# SmartToy_Main_Board_REV02_Schematic.net
KiCad netlist of a schematic drawn in Altium Designer
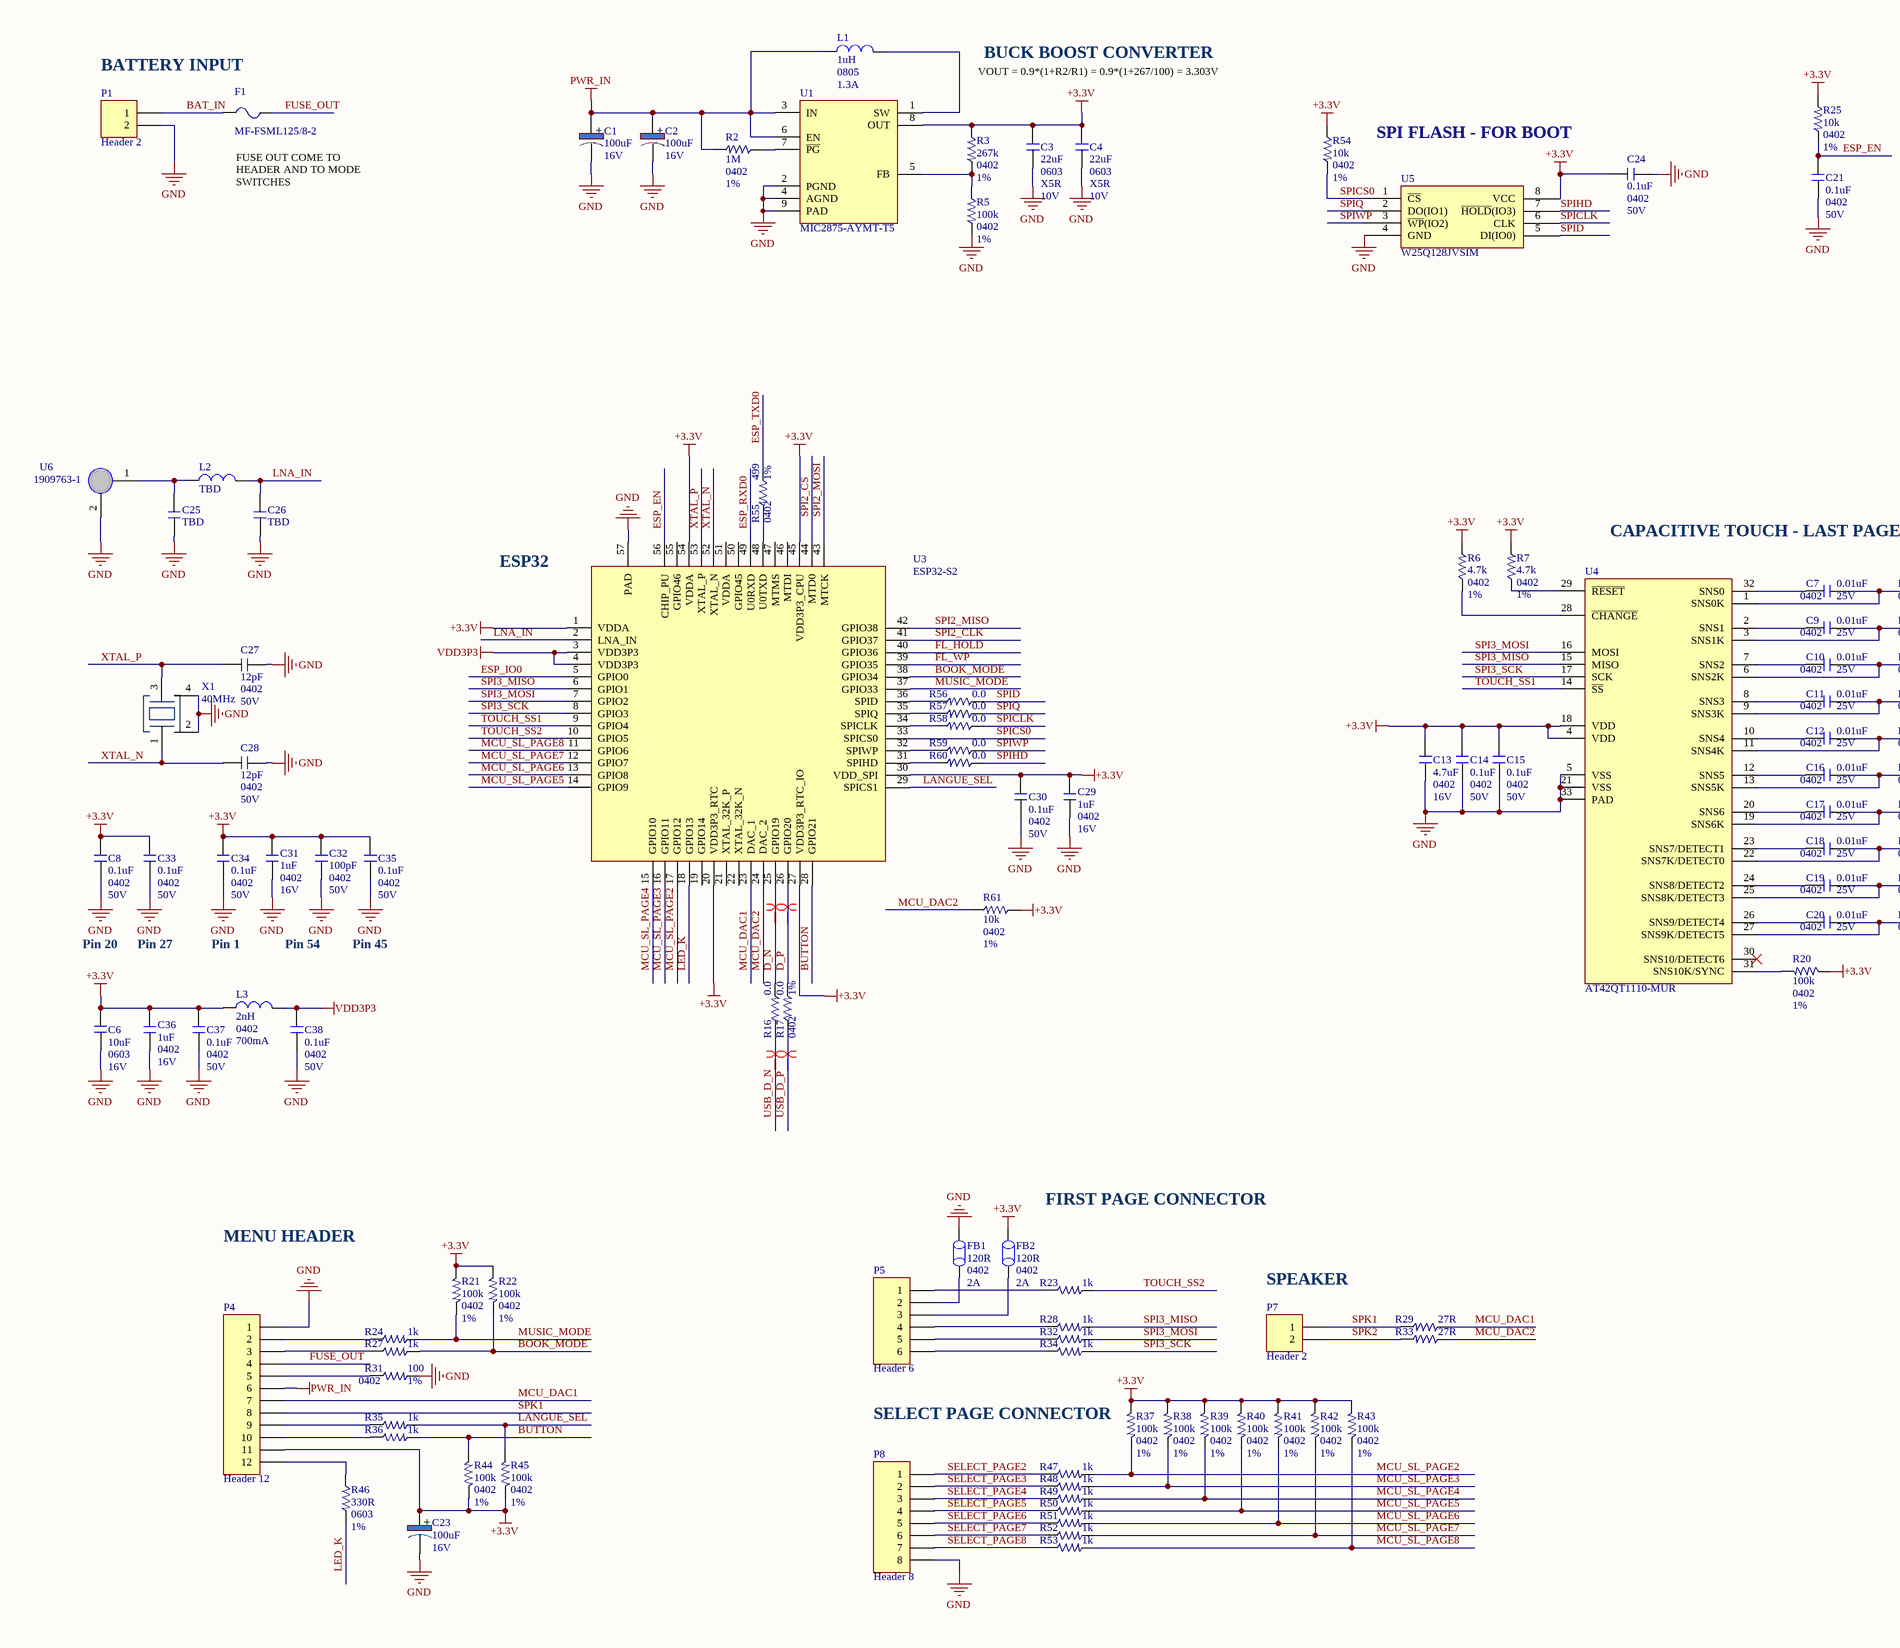
[diagram p0: SmartToy Main Board REV02 Schematic.SchDoc, left]
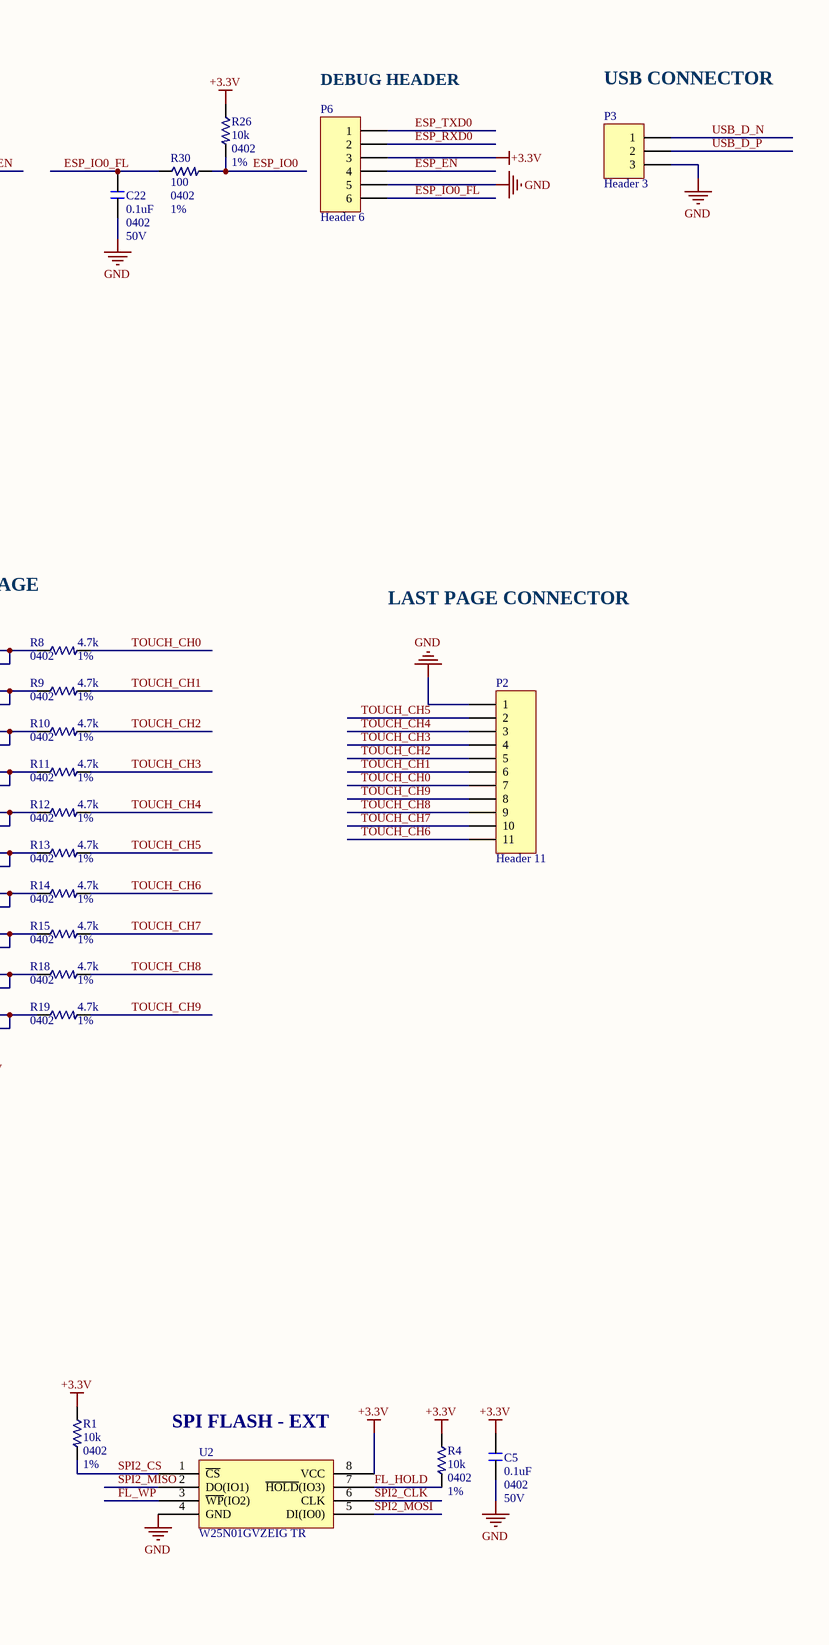
[diagram p1: SmartToy Main Board REV02 Schematic.SchDoc, right]

(export (version "E")
  (design (tool "Eeschema 10.0.6"))
  (components
    (comp (ref "C1")
      (value "100uF")
      (footprint "CP_6.3X12.5_P2.5MM")
      (description "CAP ALUM 100UF 20% 16V RADIAL")
      (fields
        (field (name "TOLERANCE") "20%")
        (field (name "VOLTAGE RATING") "16V")
        (field (name "VOLTAGE") "16V")
      )
      (libsource (lib "CommonLib") (part "CAP_PL"))
    )
    (comp (ref "C2")
      (value "100uF")
      (footprint "CP_6.3X12.5_P2.5MM")
      (description "CAP ALUM 100UF 20% 16V RADIAL")
      (fields
        (field (name "TOLERANCE") "20%")
        (field (name "VOLTAGE RATING") "16V")
        (field (name "VOLTAGE") "16V")
      )
      (libsource (lib "CommonLib") (part "CAP_PL"))
    )
    (comp (ref "C3")
      (value "22uF")
      (footprint "C0603M")
      (description "CAP CER 22UF 10V X5R 0603")
      (fields
        (field (name "MANUFACTURER") "Samsung")
        (field (name "MANUFACTURER PART NUMBER") "CL10A226MP8NUNE")
        (field (name "CASE CODE (IMPERIAL)") "0603")
        (field (name "DIELECTRIC") "X5R")
        (field (name "VOLTAGE RATING") "10V")
      )
      (libsource (lib "CommonLib") (part "CAP_CER"))
    )
    (comp (ref "C4")
      (value "22uF")
      (footprint "C0603M")
      (description "CAP CER 22UF 10V X5R 0603")
      (fields
        (field (name "MANUFACTURER") "Samsung")
        (field (name "MANUFACTURER PART NUMBER") "CL10A226MP8NUNE")
        (field (name "CASE CODE (IMPERIAL)") "0603")
        (field (name "DIELECTRIC") "X5R")
        (field (name "VOLTAGE RATING") "10V")
      )
      (libsource (lib "CommonLib") (part "CAP_CER"))
    )
    (comp (ref "C5")
      (value "0.1uF")
      (footprint "C0402M")
      (description "CAP CER 0.1UF 50V X7R 0402")
      (fields
        (field (name "MANUFACTURER") "Murata")
        (field (name "MANUFACTURER PART NUMBER") "GRM155R71H104KE14D")
        (field (name "CASE CODE (IMPERIAL)") "0402")
        (field (name "VOLTAGE") "50V")
      )
      (libsource (lib "CommonLib") (part "CAP_CER"))
    )
    (comp (ref "C6")
      (value "10uF")
      (footprint "C0603M")
      (description "CAP CER 10UF 16V X5R 0603")
      (fields
        (field (name "MANUFACTURER") "Taiyo Yuden")
        (field (name "MANUFACTURER PART NUMBER") "EMK107BBJ106MA-T")
        (field (name "CASE/PACKAGE") "0603")
        (field (name "VOLTAGE RATING (DC)") "16V")
      )
      (libsource (lib "CommonLib") (part "CAP_CER"))
    )
    (comp (ref "C7")
      (value "0.01uF")
      (footprint "C0402M")
      (description "CAP CER 10000PF 25V X7R 0402")
      (fields
        (field (name "MANUFACTURER") "Samsung")
        (field (name "MANUFACTURER PART NUMBER") "CL05B103KA5NNNC")
        (field (name "CASE/PACKAGE") "0402")
        (field (name "VOLTAGE RATING") "25V")
      )
      (libsource (lib "CommonLib") (part "CAP_CER"))
    )
    (comp (ref "C8")
      (value "0.1uF")
      (footprint "C0402M")
      (description "CAP CER 0.1UF 50V X7R 0402")
      (fields
        (field (name "MANUFACTURER") "Murata")
        (field (name "MANUFACTURER PART NUMBER") "GRM155R71H104KE14D")
        (field (name "CASE CODE (IMPERIAL)") "0402")
        (field (name "VOLTAGE") "50V")
      )
      (libsource (lib "CommonLib") (part "CAP_CER"))
    )
    (comp (ref "C9")
      (value "0.01uF")
      (footprint "C0402M")
      (description "CAP CER 10000PF 25V X7R 0402")
      (fields
        (field (name "MANUFACTURER") "Samsung")
        (field (name "MANUFACTURER PART NUMBER") "CL05B103KA5NNNC")
        (field (name "CASE/PACKAGE") "0402")
        (field (name "VOLTAGE RATING") "25V")
      )
      (libsource (lib "CommonLib") (part "CAP_CER"))
    )
    (comp (ref "C10")
      (value "0.01uF")
      (footprint "C0402M")
      (description "CAP CER 10000PF 25V X7R 0402")
      (fields
        (field (name "MANUFACTURER") "Samsung")
        (field (name "MANUFACTURER PART NUMBER") "CL05B103KA5NNNC")
        (field (name "CASE/PACKAGE") "0402")
        (field (name "VOLTAGE RATING") "25V")
      )
      (libsource (lib "CommonLib") (part "CAP_CER"))
    )
    (comp (ref "C11")
      (value "0.01uF")
      (footprint "C0402M")
      (description "CAP CER 10000PF 25V X7R 0402")
      (fields
        (field (name "MANUFACTURER") "Samsung")
        (field (name "MANUFACTURER PART NUMBER") "CL05B103KA5NNNC")
        (field (name "CASE/PACKAGE") "0402")
        (field (name "VOLTAGE RATING") "25V")
      )
      (libsource (lib "CommonLib") (part "CAP_CER"))
    )
    (comp (ref "C12")
      (value "0.01uF")
      (footprint "C0402M")
      (description "CAP CER 10000PF 25V X7R 0402")
      (fields
        (field (name "MANUFACTURER") "Samsung")
        (field (name "MANUFACTURER PART NUMBER") "CL05B103KA5NNNC")
        (field (name "CASE/PACKAGE") "0402")
        (field (name "VOLTAGE RATING") "25V")
      )
      (libsource (lib "CommonLib") (part "CAP_CER"))
    )
    (comp (ref "C13")
      (value "4.7uF")
      (footprint "C0402M")
      (description "CAP CER 4.7UF 16V X5R 0402")
      (fields
        (field (name "MANUFACTURER") "Samsung")
        (field (name "MANUFACTURER PART NUMBER") "CL05A475MO5NUNC")
        (field (name "CASE/PACKAGE") "0402")
        (field (name "VOLTAGE RATING") "16V")
      )
      (libsource (lib "CommonLib") (part "CAP_CER"))
    )
    (comp (ref "C14")
      (value "0.1uF")
      (footprint "C0402M")
      (description "CAP CER 0.1UF 50V X7R 0402")
      (fields
        (field (name "MANUFACTURER") "Murata")
        (field (name "MANUFACTURER PART NUMBER") "GRM155R71H104KE14D")
        (field (name "CASE/PACKAGE") "0402")
        (field (name "VOLTAGE") "50V")
      )
      (libsource (lib "CommonLib") (part "CAP_CER"))
    )
    (comp (ref "C15")
      (value "0.1uF")
      (footprint "C0402M")
      (description "CAP CER 0.1UF 50V X7R 0402")
      (fields
        (field (name "MANUFACTURER") "Murata")
        (field (name "MANUFACTURER PART NUMBER") "GRM155R71H104KE14D")
        (field (name "CASE/PACKAGE") "0402")
        (field (name "VOLTAGE") "50V")
      )
      (libsource (lib "CommonLib") (part "CAP_CER"))
    )
    (comp (ref "C16")
      (value "0.01uF")
      (footprint "C0402M")
      (description "CAP CER 10000PF 25V X7R 0402")
      (fields
        (field (name "MANUFACTURER") "Samsung")
        (field (name "MANUFACTURER PART NUMBER") "CL05B103KA5NNNC")
        (field (name "CASE/PACKAGE") "0402")
        (field (name "VOLTAGE RATING") "25V")
      )
      (libsource (lib "CommonLib") (part "CAP_CER"))
    )
    (comp (ref "C17")
      (value "0.01uF")
      (footprint "C0402M")
      (description "CAP CER 10000PF 25V X7R 0402")
      (fields
        (field (name "MANUFACTURER") "Samsung")
        (field (name "MANUFACTURER PART NUMBER") "CL05B103KA5NNNC")
        (field (name "CASE/PACKAGE") "0402")
        (field (name "VOLTAGE RATING") "25V")
      )
      (libsource (lib "CommonLib") (part "CAP_CER"))
    )
    (comp (ref "C18")
      (value "0.01uF")
      (footprint "C0402M")
      (description "CAP CER 10000PF 25V X7R 0402")
      (fields
        (field (name "MANUFACTURER") "Samsung")
        (field (name "MANUFACTURER PART NUMBER") "CL05B103KA5NNNC")
        (field (name "CASE/PACKAGE") "0402")
        (field (name "VOLTAGE RATING") "25V")
      )
      (libsource (lib "CommonLib") (part "CAP_CER"))
    )
    (comp (ref "C19")
      (value "0.01uF")
      (footprint "C0402M")
      (description "CAP CER 10000PF 25V X7R 0402")
      (fields
        (field (name "MANUFACTURER") "Samsung")
        (field (name "MANUFACTURER PART NUMBER") "CL05B103KA5NNNC")
        (field (name "CASE/PACKAGE") "0402")
        (field (name "VOLTAGE RATING") "25V")
      )
      (libsource (lib "CommonLib") (part "CAP_CER"))
    )
    (comp (ref "C20")
      (value "0.01uF")
      (footprint "C0402M")
      (description "CAP CER 10000PF 25V X7R 0402")
      (fields
        (field (name "MANUFACTURER") "Samsung")
        (field (name "MANUFACTURER PART NUMBER") "CL05B103KA5NNNC")
        (field (name "CASE/PACKAGE") "0402")
        (field (name "VOLTAGE RATING") "25V")
      )
      (libsource (lib "CommonLib") (part "CAP_CER"))
    )
    (comp (ref "C21")
      (value "0.1uF")
      (footprint "C0402M")
      (description "CAP CER 0.1UF 50V X7R 0402")
      (fields
        (field (name "MANUFACTURER") "Murata")
        (field (name "MANUFACTURER PART NUMBER") "GRM155R71H104KE14D")
        (field (name "CASE CODE (IMPERIAL)") "0402")
        (field (name "VOLTAGE") "50V")
      )
      (libsource (lib "CommonLib") (part "CAP_CER"))
    )
    (comp (ref "C22")
      (value "0.1uF")
      (footprint "C0402M")
      (description "CAP CER 0.1UF 50V X7R 0402")
      (fields
        (field (name "MANUFACTURER") "Murata")
        (field (name "MANUFACTURER PART NUMBER") "GRM155R71H104KE14D")
        (field (name "CASE CODE (IMPERIAL)") "0402")
        (field (name "VOLTAGE") "50V")
      )
      (libsource (lib "CommonLib") (part "CAP_CER"))
    )
    (comp (ref "C23")
      (value "100uF")
      (footprint "CP_6.3X12.5_P2.5MM")
      (description "CAP ALUM 100UF 20% 16V RADIAL")
      (fields
        (field (name "TOLERANCE") "20%")
        (field (name "VOLTAGE RATING") "16V")
        (field (name "VOLTAGE") "16V")
      )
      (libsource (lib "CommonLib") (part "CAP_PL"))
    )
    (comp (ref "C24")
      (value "0.1uF")
      (footprint "C0402M")
      (description "CAP CER 0.1UF 50V X7R 0402")
      (fields
        (field (name "MANUFACTURER") "Murata")
        (field (name "MANUFACTURER PART NUMBER") "GRM155R71H104KE14D")
        (field (name "CASE CODE (IMPERIAL)") "0402")
        (field (name "VOLTAGE") "50V")
      )
      (libsource (lib "CommonLib") (part "CAP_CER"))
    )
    (comp (ref "C25")
      (value "TBD")
      (footprint "C0402M")
      (description "CERAMIC CAPACITOR")
      (libsource (lib "") (part "CAP_CER_1"))
    )
    (comp (ref "C26")
      (value "TBD")
      (footprint "C0402M")
      (description "CERAMIC CAPACITOR")
      (libsource (lib "") (part "CAP_CER_1"))
    )
    (comp (ref "C27")
      (value "12pF")
      (footprint "C0402M")
      (description "CAP CER 12PF 50V C0G/NP0 0402")
      (fields
        (field (name "MANUFACTURER") "Murata")
        (field (name "MANUFACTURER PART NUMBER") "GRM1555C1H120JA01J")
        (field (name "CASE/PACKAGE") "0402")
        (field (name "VOLTAGE RATING") "50V")
      )
      (libsource (lib "CommonLib") (part "CAP_CER"))
    )
    (comp (ref "C28")
      (value "12pF")
      (footprint "C0402M")
      (description "CAP CER 12PF 50V C0G/NP0 0402")
      (fields
        (field (name "MANUFACTURER") "Murata")
        (field (name "MANUFACTURER PART NUMBER") "GRM1555C1H120JA01J")
        (field (name "CASE/PACKAGE") "0402")
        (field (name "VOLTAGE RATING") "50V")
      )
      (libsource (lib "CommonLib") (part "CAP_CER"))
    )
    (comp (ref "C29")
      (value "1uF")
      (footprint "C0402M")
      (description "CAP CER 1UF 16V X5R 0402")
      (fields
        (field (name "CASE/PACKAGE") "0402")
        (field (name "VOLTAGE RATING") "16V")
        (field (name "TOLERANCE") "20%")
      )
      (libsource (lib "") (part "CAP_CER_1"))
    )
    (comp (ref "C30")
      (value "0.1uF")
      (footprint "C0402M")
      (description "CAP CER 0.1UF 50V X7R 0402")
      (fields
        (field (name "MANUFACTURER") "Murata")
        (field (name "MANUFACTURER PART NUMBER") "GRM155R71H104KE14D")
        (field (name "CASE CODE (IMPERIAL)") "0402")
        (field (name "VOLTAGE") "50V")
      )
      (libsource (lib "CommonLib") (part "CAP_CER"))
    )
    (comp (ref "C31")
      (value "1uF")
      (footprint "C0402M")
      (description "CAP CER 1UF 16V X5R 0402")
      (fields
        (field (name "CASE/PACKAGE") "0402")
        (field (name "VOLTAGE RATING") "16V")
        (field (name "TOLERANCE") "20%")
      )
      (libsource (lib "") (part "CAP_CER_1"))
    )
    (comp (ref "C32")
      (value "100pF")
      (footprint "C0402M")
      (description "CAP CER 100PF 50V X7R 0402")
      (fields
        (field (name "CASE/PACKAGE") "0402")
        (field (name "TOLERANCE") "10%")
        (field (name "VOLTAGE RATING (DC)") "50V")
        (field (name "VOLTAGE") "50V")
      )
      (libsource (lib "") (part "CAP_CER_1"))
    )
    (comp (ref "C33")
      (value "0.1uF")
      (footprint "C0402M")
      (description "CAP CER 0.1UF 50V X7R 0402")
      (fields
        (field (name "MANUFACTURER") "Murata")
        (field (name "MANUFACTURER PART NUMBER") "GRM155R71H104KE14D")
        (field (name "CASE CODE (IMPERIAL)") "0402")
        (field (name "VOLTAGE") "50V")
      )
      (libsource (lib "CommonLib") (part "CAP_CER"))
    )
    (comp (ref "C34")
      (value "0.1uF")
      (footprint "C0402M")
      (description "CAP CER 0.1UF 50V X7R 0402")
      (fields
        (field (name "MANUFACTURER") "Murata")
        (field (name "MANUFACTURER PART NUMBER") "GRM155R71H104KE14D")
        (field (name "CASE CODE (IMPERIAL)") "0402")
        (field (name "VOLTAGE") "50V")
      )
      (libsource (lib "CommonLib") (part "CAP_CER"))
    )
    (comp (ref "C35")
      (value "0.1uF")
      (footprint "C0402M")
      (description "CAP CER 0.1UF 50V X7R 0402")
      (fields
        (field (name "MANUFACTURER") "Murata")
        (field (name "MANUFACTURER PART NUMBER") "GRM155R71H104KE14D")
        (field (name "CASE CODE (IMPERIAL)") "0402")
        (field (name "VOLTAGE") "50V")
      )
      (libsource (lib "CommonLib") (part "CAP_CER"))
    )
    (comp (ref "C36")
      (value "1uF")
      (footprint "C0402M")
      (description "CAP CER 1UF 16V X5R 0402")
      (fields
        (field (name "CASE/PACKAGE") "0402")
        (field (name "VOLTAGE RATING") "16V")
        (field (name "TOLERANCE") "20%")
      )
      (libsource (lib "") (part "CAP_CER_1"))
    )
    (comp (ref "C37")
      (value "0.1uF")
      (footprint "C0402M")
      (description "CAP CER 0.1UF 50V X7R 0402")
      (fields
        (field (name "MANUFACTURER") "Murata")
        (field (name "MANUFACTURER PART NUMBER") "GRM155R71H104KE14D")
        (field (name "CASE CODE (IMPERIAL)") "0402")
        (field (name "VOLTAGE") "50V")
      )
      (libsource (lib "CommonLib") (part "CAP_CER"))
    )
    (comp (ref "C38")
      (value "0.1uF")
      (footprint "C0402M")
      (description "CAP CER 0.1UF 50V X7R 0402")
      (fields
        (field (name "MANUFACTURER") "Murata")
        (field (name "MANUFACTURER PART NUMBER") "GRM155R71H104KE14D")
        (field (name "CASE CODE (IMPERIAL)") "0402")
        (field (name "VOLTAGE") "50V")
      )
      (libsource (lib "CommonLib") (part "CAP_CER"))
    )
    (comp (ref "F1")
      (value "MF-FSML125/8-2")
      (footprint "R0603M")
      (description "PTC RESET FUSE 8V 1.25A 0603")
      (libsource (lib "CommonLib") (part "FUSE"))
    )
    (comp (ref "FB1")
      (value "120R")
      (footprint "R0402M")
      (description "FERRITE BEAD 120 OHM 0402 1LN")
      (fields
        (field (name "MANUFACTURER") "Murata")
        (field (name "MANUFACTURER PART NUMBER") "BLM15PX121SN1D")
        (field (name "CASE/PACKAGE") "0402")
        (field (name "CURRENT RATING") "2A")
      )
      (libsource (lib "CommonLib") (part "FB"))
    )
    (comp (ref "FB2")
      (value "120R")
      (footprint "R0402M")
      (description "FERRITE BEAD 120 OHM 0402 1LN")
      (fields
        (field (name "MANUFACTURER") "Murata")
        (field (name "MANUFACTURER PART NUMBER") "BLM15PX121SN1D")
        (field (name "CASE/PACKAGE") "0402")
        (field (name "CURRENT RATING") "2A")
      )
      (libsource (lib "CommonLib") (part "FB"))
    )
    (comp (ref "L1")
      (value "1uH")
      (footprint "IND_0805")
      (description "FIXED IND 1UH 1.3A 82.5 MOHM SMD")
      (fields
        (field (name "CASE CODE (IMPERIAL)") "0805")
        (field (name "TOLERANCE") "30%")
        (field (name "CURRENT RATING") "1.3A")
      )
      (libsource (lib "CommonLib") (part "IND_SMD"))
    )
    (comp (ref "L2")
      (value "TBD")
      (footprint "IND_0402")
      (description "INDUCTOR SMD")
      (libsource (lib "CommonLib") (part "IND_SMD"))
    )
    (comp (ref "L3")
      (value "2nH")
      (footprint "IND_0402")
      (description "FIXED IND 2NH 700MA 120 MOHM SMD")
      (fields (field (name "CASE CODE (IMPERIAL)") "0402") (field (name "CURRENT RATING") "700mA"))
      (libsource (lib "CommonLib") (part "IND_SMD"))
    )
    (comp (ref "P1")
      (value "Header 2")
      (footprint "HDR1X2")
      (description "Header, 2-Pin")
      (fields (field (name "PUBLISHER") "Altium Limited"))
      (libsource (lib "Miscellaneous Connectors") (part "Header 2"))
    )
    (comp (ref "P2")
      (value "Header 11")
      (footprint "TOUCH_CONTACT_MAINBOARD")
      (description "Header, 11-Pin")
      (fields (field (name "PUBLISHER") "Altium Limited"))
      (libsource (lib "Miscellaneous Connectors") (part "Header 11"))
    )
    (comp (ref "P3")
      (value "Header 3")
      (footprint "HDR1X3")
      (description "Header, 3-Pin")
      (fields (field (name "PUBLISHER") "Altium Limited"))
      (libsource (lib "Miscellaneous Connectors") (part "Header 3"))
    )
    (comp (ref "P4")
      (value "Header 12")
      (footprint "HDR1X12")
      (description "Header, 12-Pin")
      (fields (field (name "PUBLISHER") "Altium Limited"))
      (libsource (lib "Miscellaneous Connectors") (part "Header 12"))
    )
    (comp (ref "P5")
      (value "Header 6")
      (footprint "HDR1X6")
      (description "Header, 6-Pin")
      (fields (field (name "PUBLISHER") "Altium Limited"))
      (libsource (lib "Miscellaneous Connectors") (part "Header 6"))
    )
    (comp (ref "P6")
      (value "Header 6")
      (footprint "HDR1X6")
      (description "Header, 6-Pin")
      (fields (field (name "PUBLISHER") "Altium Limited"))
      (libsource (lib "Miscellaneous Connectors") (part "Header 6"))
    )
    (comp (ref "P7")
      (value "Header 2")
      (footprint "HDR1X2")
      (description "Header, 2-Pin")
      (fields (field (name "PUBLISHER") "Altium Limited"))
      (libsource (lib "Miscellaneous Connectors") (part "Header 2"))
    )
    (comp (ref "P8")
      (value "Header 8")
      (footprint "HDR1X8")
      (description "Header, 8-Pin")
      (fields (field (name "PUBLISHER") "Altium Limited"))
      (libsource (lib "Miscellaneous Connectors") (part "Header 8"))
    )
    (comp (ref "R1")
      (value "10k")
      (footprint "R0402M")
      (description "RES SMD 10K OHM 1% 1/16W 0402")
      (fields
        (field (name "MANUFACTURER") "Yageo")
        (field (name "MANUFACTURER PART NUMBER") "RC0402FR-0710KL")
        (field (name "CASE CODE (IMPERIAL)") "0402")
        (field (name "TOLERANCE") "1%")
      )
      (libsource (lib "CommonLib") (part "RES_SMD"))
    )
    (comp (ref "R2")
      (value "1M")
      (footprint "R0402M")
      (description "RES SMD 1M OHM 1% 1/16W 0402")
      (fields (field (name "SIZE CODE") "0402") (field (name "TOLERANCE") "1%"))
      (libsource (lib "CommonLib") (part "RES_SMD"))
    )
    (comp (ref "R3")
      (value "267k")
      (footprint "R0402M")
      (description "RES SMD 267k OHM 1% 1/16W 0402")
      (fields (field (name "CASE/PACKAGE") "0402") (field (name "TOLERANCE") "1%"))
      (libsource (lib "CommonLib") (part "RES_SMD"))
    )
    (comp (ref "R4")
      (value "10k")
      (footprint "R0402M")
      (description "RES SMD 10K OHM 1% 1/16W 0402")
      (fields
        (field (name "MANUFACTURER") "Yageo")
        (field (name "MANUFACTURER PART NUMBER") "RC0402FR-0710KL")
        (field (name "CASE CODE (IMPERIAL)") "0402")
        (field (name "TOLERANCE") "1%")
      )
      (libsource (lib "CommonLib") (part "RES_SMD"))
    )
    (comp (ref "R5")
      (value "100k")
      (footprint "R0402M")
      (description "RES SMD 100K OHM 1% 1/16W 0402")
      (fields
        (field (name "CASE/PACKAGE") "0402")
        (field (name "TOLERANCE") "1%")
        (field (name "RESISTANCE TOLERANCE") "1%")
      )
      (libsource (lib "CommonLib") (part "RES_SMD"))
    )
    (comp (ref "R6")
      (value "4.7k")
      (footprint "R0402M")
      (description "RES SMD 4.7K OHM 1% 1/16W 0402")
      (fields
        (field (name "MANUFACTURER") "Yageo")
        (field (name "MANUFACTURER PART NUMBER") "RC0402FR-074K7L")
        (field (name "CASE CODE (IMPERIAL)") "0402")
        (field (name "TOLERANCE") "1%")
      )
      (libsource (lib "CommonLib") (part "RES_SMD"))
    )
    (comp (ref "R7")
      (value "4.7k")
      (footprint "R0402M")
      (description "RES SMD 4.7K OHM 1% 1/16W 0402")
      (fields
        (field (name "MANUFACTURER") "Yageo")
        (field (name "MANUFACTURER PART NUMBER") "RC0402FR-074K7L")
        (field (name "CASE CODE (IMPERIAL)") "0402")
        (field (name "TOLERANCE") "1%")
      )
      (libsource (lib "CommonLib") (part "RES_SMD"))
    )
    (comp (ref "R8")
      (value "4.7k")
      (footprint "R0402M")
      (description "RES SMD 4.7K OHM 1% 1/16W 0402")
      (fields
        (field (name "MANUFACTURER") "Yageo")
        (field (name "MANUFACTURER PART NUMBER") "RC0402FR-074K7L")
        (field (name "CASE CODE (IMPERIAL)") "0402")
        (field (name "TOLERANCE") "1%")
      )
      (libsource (lib "CommonLib") (part "RES_SMD"))
    )
    (comp (ref "R9")
      (value "4.7k")
      (footprint "R0402M")
      (description "RES SMD 4.7K OHM 1% 1/16W 0402")
      (fields
        (field (name "MANUFACTURER") "Yageo")
        (field (name "MANUFACTURER PART NUMBER") "RC0402FR-074K7L")
        (field (name "CASE CODE (IMPERIAL)") "0402")
        (field (name "TOLERANCE") "1%")
      )
      (libsource (lib "CommonLib") (part "RES_SMD"))
    )
    (comp (ref "R10")
      (value "4.7k")
      (footprint "R0402M")
      (description "RES SMD 4.7K OHM 1% 1/16W 0402")
      (fields
        (field (name "MANUFACTURER") "Yageo")
        (field (name "MANUFACTURER PART NUMBER") "RC0402FR-074K7L")
        (field (name "CASE CODE (IMPERIAL)") "0402")
        (field (name "TOLERANCE") "1%")
      )
      (libsource (lib "CommonLib") (part "RES_SMD"))
    )
    (comp (ref "R11")
      (value "4.7k")
      (footprint "R0402M")
      (description "RES SMD 4.7K OHM 1% 1/16W 0402")
      (fields
        (field (name "MANUFACTURER") "Yageo")
        (field (name "MANUFACTURER PART NUMBER") "RC0402FR-074K7L")
        (field (name "CASE CODE (IMPERIAL)") "0402")
        (field (name "TOLERANCE") "1%")
      )
      (libsource (lib "CommonLib") (part "RES_SMD"))
    )
    (comp (ref "R12")
      (value "4.7k")
      (footprint "R0402M")
      (description "RES SMD 4.7K OHM 1% 1/16W 0402")
      (fields
        (field (name "MANUFACTURER") "Yageo")
        (field (name "MANUFACTURER PART NUMBER") "RC0402FR-074K7L")
        (field (name "CASE CODE (IMPERIAL)") "0402")
        (field (name "TOLERANCE") "1%")
      )
      (libsource (lib "CommonLib") (part "RES_SMD"))
    )
    (comp (ref "R13")
      (value "4.7k")
      (footprint "R0402M")
      (description "RES SMD 4.7K OHM 1% 1/16W 0402")
      (fields
        (field (name "MANUFACTURER") "Yageo")
        (field (name "MANUFACTURER PART NUMBER") "RC0402FR-074K7L")
        (field (name "CASE CODE (IMPERIAL)") "0402")
        (field (name "TOLERANCE") "1%")
      )
      (libsource (lib "CommonLib") (part "RES_SMD"))
    )
    (comp (ref "R14")
      (value "4.7k")
      (footprint "R0402M")
      (description "RES SMD 4.7K OHM 1% 1/16W 0402")
      (fields
        (field (name "MANUFACTURER") "Yageo")
        (field (name "MANUFACTURER PART NUMBER") "RC0402FR-074K7L")
        (field (name "CASE CODE (IMPERIAL)") "0402")
        (field (name "TOLERANCE") "1%")
      )
      (libsource (lib "CommonLib") (part "RES_SMD"))
    )
    (comp (ref "R15")
      (value "4.7k")
      (footprint "R0402M")
      (description "RES SMD 4.7K OHM 1% 1/16W 0402")
      (fields
        (field (name "MANUFACTURER") "Yageo")
        (field (name "MANUFACTURER PART NUMBER") "RC0402FR-074K7L")
        (field (name "CASE CODE (IMPERIAL)") "0402")
        (field (name "TOLERANCE") "1%")
      )
      (libsource (lib "CommonLib") (part "RES_SMD"))
    )
    (comp (ref "R16")
      (value "0.0")
      (footprint "R0402M")
      (description "RES SMD 0 OHM JUMPER 1/16W 0402")
      (fields
        (field (name "MANUFACTURER") "Yageo")
        (field (name "MANUFACTURER PART NUMBER") "RC0402FR-070RL")
      )
      (libsource (lib "CommonLib") (part "RES_SMD"))
    )
    (comp (ref "R17")
      (value "0.0")
      (footprint "R0402M")
      (description "RES SMD 0 OHM JUMPER 1/16W 0402")
      (fields
        (field (name "MANUFACTURER") "Yageo")
        (field (name "MANUFACTURER PART NUMBER") "RC0402FR-070RL")
        (field (name "CASE CODE (IMPERIAL)") "0402")
        (field (name "TOLERANCE") "1%")
      )
      (libsource (lib "CommonLib") (part "RES_SMD"))
    )
    (comp (ref "R18")
      (value "4.7k")
      (footprint "R0402M")
      (description "RES SMD 4.7K OHM 1% 1/16W 0402")
      (fields
        (field (name "MANUFACTURER") "Yageo")
        (field (name "MANUFACTURER PART NUMBER") "RC0402FR-074K7L")
        (field (name "CASE CODE (IMPERIAL)") "0402")
        (field (name "TOLERANCE") "1%")
      )
      (libsource (lib "CommonLib") (part "RES_SMD"))
    )
    (comp (ref "R19")
      (value "4.7k")
      (footprint "R0402M")
      (description "RES SMD 4.7K OHM 1% 1/16W 0402")
      (fields
        (field (name "MANUFACTURER") "Yageo")
        (field (name "MANUFACTURER PART NUMBER") "RC0402FR-074K7L")
        (field (name "CASE CODE (IMPERIAL)") "0402")
        (field (name "TOLERANCE") "1%")
      )
      (libsource (lib "CommonLib") (part "RES_SMD"))
    )
    (comp (ref "R20")
      (value "100k")
      (footprint "R0402M")
      (description "RES SMD 100K OHM 1% 1/16W 0402")
      (fields
        (field (name "MANUFACTURER") "Yageo")
        (field (name "MANUFACTURER PART NUMBER") "RC0402FR-07100KL")
        (field (name "CASE CODE (IMPERIAL)") "0402")
        (field (name "TOLERANCE") "1%")
      )
      (libsource (lib "BLE1") (part "RES_SMD"))
    )
    (comp (ref "R21")
      (value "100k")
      (footprint "R0402M")
      (description "RES SMD 100K OHM 1% 1/16W 0402")
      (fields
        (field (name "MANUFACTURER") "Yageo")
        (field (name "MANUFACTURER PART NUMBER") "RC0402FR-07100KL")
        (field (name "CASE CODE (IMPERIAL)") "0402")
        (field (name "TOLERANCE") "1%")
      )
      (libsource (lib "BLE1") (part "RES_SMD"))
    )
    (comp (ref "R22")
      (value "100k")
      (footprint "R0402M")
      (description "RES SMD 100K OHM 1% 1/16W 0402")
      (fields
        (field (name "MANUFACTURER") "Yageo")
        (field (name "MANUFACTURER PART NUMBER") "RC0402FR-07100KL")
        (field (name "CASE CODE (IMPERIAL)") "0402")
        (field (name "TOLERANCE") "1%")
      )
      (libsource (lib "BLE1") (part "RES_SMD"))
    )
    (comp (ref "R23")
      (value "1k")
      (footprint "R0402M")
      (description "Surface Mount Chip Resistor, Thick Film, RC Series, 1 kohm, 62.5 mW, 1%, 50 V, 0402 [1005 Metric]")
      (fields (field (name "TOLERANCE") "1%"))
      (libsource (lib "CommonLib") (part "RES_SMD"))
    )
    (comp (ref "R24")
      (value "1k")
      (footprint "R0402M")
      (description "Surface Mount Chip Resistor, Thick Film, RC Series, 1 kohm, 62.5 mW, 1%, 50 V, 0402 [1005 Metric]")
      (fields (field (name "TOLERANCE") "1%"))
      (libsource (lib "CommonLib") (part "RES_SMD"))
    )
    (comp (ref "R25")
      (value "10k")
      (footprint "R0402M")
      (description "RES SMD 10K OHM 1% 1/16W 0402")
      (fields
        (field (name "MANUFACTURER") "Yageo")
        (field (name "MANUFACTURER PART NUMBER") "RC0402FR-0710KL")
        (field (name "CASE CODE (IMPERIAL)") "0402")
        (field (name "TOLERANCE") "1%")
      )
      (libsource (lib "CommonLib") (part "RES_SMD"))
    )
    (comp (ref "R26")
      (value "10k")
      (footprint "R0402M")
      (description "RES SMD 10K OHM 1% 1/16W 0402")
      (fields
        (field (name "MANUFACTURER") "Yageo")
        (field (name "MANUFACTURER PART NUMBER") "RC0402FR-0710KL")
        (field (name "CASE CODE (IMPERIAL)") "0402")
        (field (name "TOLERANCE") "1%")
      )
      (libsource (lib "CommonLib") (part "RES_SMD"))
    )
    (comp (ref "R27")
      (value "1k")
      (footprint "R0402M")
      (description "Surface Mount Chip Resistor, Thick Film, RC Series, 1 kohm, 62.5 mW, 1%, 50 V, 0402 [1005 Metric]")
      (fields (field (name "TOLERANCE") "1%"))
      (libsource (lib "CommonLib") (part "RES_SMD"))
    )
    (comp (ref "R28")
      (value "1k")
      (footprint "R0402M")
      (description "Surface Mount Chip Resistor, Thick Film, RC Series, 1 kohm, 62.5 mW, 1%, 50 V, 0402 [1005 Metric]")
      (fields (field (name "TOLERANCE") "1%"))
      (libsource (lib "CommonLib") (part "RES_SMD"))
    )
    (comp (ref "R29")
      (value "27R")
      (footprint "R0402M")
      (fields (field (name "TOLERANCE") "1%"))
      (libsource (lib "CommonLib") (part "RES_SMD"))
    )
    (comp (ref "R30")
      (value "100")
      (footprint "R0402M")
      (description "RES SMD 100 OHM 5% 1/16W 0402")
      (fields
        (field (name "MANUFACTURER") "Yageo")
        (field (name "MANUFACTURER PART NUMBER") "RC0402FR-07100RL")
        (field (name "CASE CODE (IMPERIAL)") "0402")
        (field (name "TOLERANCE") "1%")
      )
      (libsource (lib "CommonLib") (part "RES_SMD"))
    )
    (comp (ref "R31")
      (value "100")
      (footprint "R0402M")
      (description "RES SMD 100 OHM 5% 1/16W 0402")
      (fields
        (field (name "MANUFACTURER") "Yageo")
        (field (name "MANUFACTURER PART NUMBER") "RC0402FR-07100RL")
        (field (name "CASE CODE (IMPERIAL)") "0402")
        (field (name "TOLERANCE") "1%")
      )
      (libsource (lib "CommonLib") (part "RES_SMD"))
    )
    (comp (ref "R32")
      (value "1k")
      (footprint "R0402M")
      (description "Surface Mount Chip Resistor, Thick Film, RC Series, 1 kohm, 62.5 mW, 1%, 50 V, 0402 [1005 Metric]")
      (fields (field (name "TOLERANCE") "1%"))
      (libsource (lib "CommonLib") (part "RES_SMD"))
    )
    (comp (ref "R33")
      (value "27R")
      (footprint "R0402M")
      (fields (field (name "TOLERANCE") "1%"))
      (libsource (lib "CommonLib") (part "RES_SMD"))
    )
    (comp (ref "R34")
      (value "1k")
      (footprint "R0402M")
      (description "Surface Mount Chip Resistor, Thick Film, RC Series, 1 kohm, 62.5 mW, 1%, 50 V, 0402 [1005 Metric]")
      (fields (field (name "TOLERANCE") "1%"))
      (libsource (lib "CommonLib") (part "RES_SMD"))
    )
    (comp (ref "R35")
      (value "1k")
      (footprint "R0402M")
      (description "Surface Mount Chip Resistor, Thick Film, RC Series, 1 kohm, 62.5 mW, 1%, 50 V, 0402 [1005 Metric]")
      (fields (field (name "TOLERANCE") "1%"))
      (libsource (lib "CommonLib") (part "RES_SMD"))
    )
    (comp (ref "R36")
      (value "1k")
      (footprint "R0402M")
      (description "Surface Mount Chip Resistor, Thick Film, RC Series, 1 kohm, 62.5 mW, 1%, 50 V, 0402 [1005 Metric]")
      (fields (field (name "TOLERANCE") "1%"))
      (libsource (lib "CommonLib") (part "RES_SMD"))
    )
    (comp (ref "R37")
      (value "100k")
      (footprint "R0402M")
      (description "RES SMD 100K OHM 1% 1/16W 0402")
      (fields
        (field (name "MANUFACTURER") "Yageo")
        (field (name "MANUFACTURER PART NUMBER") "RC0402FR-07100KL")
        (field (name "CASE CODE (IMPERIAL)") "0402")
        (field (name "TOLERANCE") "1%")
      )
      (libsource (lib "BLE1") (part "RES_SMD"))
    )
    (comp (ref "R38")
      (value "100k")
      (footprint "R0402M")
      (description "RES SMD 100K OHM 1% 1/16W 0402")
      (fields
        (field (name "MANUFACTURER") "Yageo")
        (field (name "MANUFACTURER PART NUMBER") "RC0402FR-07100KL")
        (field (name "CASE CODE (IMPERIAL)") "0402")
        (field (name "TOLERANCE") "1%")
      )
      (libsource (lib "BLE1") (part "RES_SMD"))
    )
    (comp (ref "R39")
      (value "100k")
      (footprint "R0402M")
      (description "RES SMD 100K OHM 1% 1/16W 0402")
      (fields
        (field (name "MANUFACTURER") "Yageo")
        (field (name "MANUFACTURER PART NUMBER") "RC0402FR-07100KL")
        (field (name "CASE CODE (IMPERIAL)") "0402")
        (field (name "TOLERANCE") "1%")
      )
      (libsource (lib "BLE1") (part "RES_SMD"))
    )
    (comp (ref "R40")
      (value "100k")
      (footprint "R0402M")
      (description "RES SMD 100K OHM 1% 1/16W 0402")
      (fields
        (field (name "MANUFACTURER") "Yageo")
        (field (name "MANUFACTURER PART NUMBER") "RC0402FR-07100KL")
        (field (name "CASE CODE (IMPERIAL)") "0402")
        (field (name "TOLERANCE") "1%")
      )
      (libsource (lib "BLE1") (part "RES_SMD"))
    )
    (comp (ref "R41")
      (value "100k")
      (footprint "R0402M")
      (description "RES SMD 100K OHM 1% 1/16W 0402")
      (fields
        (field (name "MANUFACTURER") "Yageo")
        (field (name "MANUFACTURER PART NUMBER") "RC0402FR-07100KL")
        (field (name "CASE CODE (IMPERIAL)") "0402")
        (field (name "TOLERANCE") "1%")
      )
      (libsource (lib "BLE1") (part "RES_SMD"))
    )
    (comp (ref "R42")
      (value "100k")
      (footprint "R0402M")
      (description "RES SMD 100K OHM 1% 1/16W 0402")
      (fields
        (field (name "MANUFACTURER") "Yageo")
        (field (name "MANUFACTURER PART NUMBER") "RC0402FR-07100KL")
        (field (name "CASE CODE (IMPERIAL)") "0402")
        (field (name "TOLERANCE") "1%")
      )
      (libsource (lib "BLE1") (part "RES_SMD"))
    )
    (comp (ref "R43")
      (value "100k")
      (footprint "R0402M")
      (description "RES SMD 100K OHM 1% 1/16W 0402")
      (fields
        (field (name "MANUFACTURER") "Yageo")
        (field (name "MANUFACTURER PART NUMBER") "RC0402FR-07100KL")
        (field (name "CASE CODE (IMPERIAL)") "0402")
        (field (name "TOLERANCE") "1%")
      )
      (libsource (lib "BLE1") (part "RES_SMD"))
    )
    (comp (ref "R44")
      (value "100k")
      (footprint "R0402M")
      (description "RES SMD 100K OHM 1% 1/16W 0402")
      (fields
        (field (name "MANUFACTURER") "Yageo")
        (field (name "MANUFACTURER PART NUMBER") "RC0402FR-07100KL")
        (field (name "CASE CODE (IMPERIAL)") "0402")
        (field (name "TOLERANCE") "1%")
      )
      (libsource (lib "BLE1") (part "RES_SMD"))
    )
    (comp (ref "R45")
      (value "100k")
      (footprint "R0402M")
      (description "RES SMD 100K OHM 1% 1/16W 0402")
      (fields
        (field (name "MANUFACTURER") "Yageo")
        (field (name "MANUFACTURER PART NUMBER") "RC0402FR-07100KL")
        (field (name "CASE CODE (IMPERIAL)") "0402")
        (field (name "TOLERANCE") "1%")
      )
      (libsource (lib "BLE1") (part "RES_SMD"))
    )
    (comp (ref "R46")
      (value "330R")
      (footprint "R0603M")
      (description "YAGEO (PHYCOMP) - RC0603FR-07330RL - RES, THICK FILM, 330R, 1%, 0.1W, 0603")
      (fields (field (name "CASE/PACKAGE") "0603") (field (name "TOLERANCE") "1%"))
      (libsource (lib "CommonLib") (part "RES_SMD"))
    )
    (comp (ref "R47")
      (value "1k")
      (footprint "R0402M")
      (description "Surface Mount Chip Resistor, Thick Film, RC Series, 1 kohm, 62.5 mW, 1%, 50 V, 0402 [1005 Metric]")
      (fields (field (name "TOLERANCE") "1%"))
      (libsource (lib "CommonLib") (part "RES_SMD"))
    )
    (comp (ref "R48")
      (value "1k")
      (footprint "R0402M")
      (description "Surface Mount Chip Resistor, Thick Film, RC Series, 1 kohm, 62.5 mW, 1%, 50 V, 0402 [1005 Metric]")
      (fields (field (name "TOLERANCE") "1%"))
      (libsource (lib "CommonLib") (part "RES_SMD"))
    )
    (comp (ref "R49")
      (value "1k")
      (footprint "R0402M")
      (description "Surface Mount Chip Resistor, Thick Film, RC Series, 1 kohm, 62.5 mW, 1%, 50 V, 0402 [1005 Metric]")
      (fields (field (name "TOLERANCE") "1%"))
      (libsource (lib "CommonLib") (part "RES_SMD"))
    )
    (comp (ref "R50")
      (value "1k")
      (footprint "R0402M")
      (description "Surface Mount Chip Resistor, Thick Film, RC Series, 1 kohm, 62.5 mW, 1%, 50 V, 0402 [1005 Metric]")
      (fields (field (name "TOLERANCE") "1%"))
      (libsource (lib "CommonLib") (part "RES_SMD"))
    )
    (comp (ref "R51")
      (value "1k")
      (footprint "R0402M")
      (description "Surface Mount Chip Resistor, Thick Film, RC Series, 1 kohm, 62.5 mW, 1%, 50 V, 0402 [1005 Metric]")
      (fields (field (name "TOLERANCE") "1%"))
      (libsource (lib "CommonLib") (part "RES_SMD"))
    )
    (comp (ref "R52")
      (value "1k")
      (footprint "R0402M")
      (description "Surface Mount Chip Resistor, Thick Film, RC Series, 1 kohm, 62.5 mW, 1%, 50 V, 0402 [1005 Metric]")
      (fields (field (name "TOLERANCE") "1%"))
      (libsource (lib "CommonLib") (part "RES_SMD"))
    )
    (comp (ref "R53")
      (value "1k")
      (footprint "R0402M")
      (description "Surface Mount Chip Resistor, Thick Film, RC Series, 1 kohm, 62.5 mW, 1%, 50 V, 0402 [1005 Metric]")
      (fields (field (name "TOLERANCE") "1%"))
      (libsource (lib "CommonLib") (part "RES_SMD"))
    )
    (comp (ref "R54")
      (value "10k")
      (footprint "R0402M")
      (description "RES SMD 10K OHM 1% 1/16W 0402")
      (fields
        (field (name "MANUFACTURER") "Yageo")
        (field (name "MANUFACTURER PART NUMBER") "RC0402FR-0710KL")
        (field (name "CASE CODE (IMPERIAL)") "0402")
        (field (name "TOLERANCE") "1%")
      )
      (libsource (lib "CommonLib") (part "RES_SMD"))
    )
    (comp (ref "R55")
      (value "499")
      (footprint "R0402M")
      (description "RES SMD 499 OHM 5% 1/16W 0402")
      (fields
        (field (name "CASE CODE (IMPERIAL)") "0402")
        (field (name "TOLERANCE") "1%")
        (field (name "RESISTANCE TOLERANCE") "1%")
      )
      (libsource (lib "CommonLib") (part "RES_SMD"))
    )
    (comp (ref "R56")
      (value "0.0")
      (footprint "R0402M")
      (description "RES SMD 0 OHM JUMPER 1/16W 0402")
      (fields (field (name "TOLERANCE") "1%"))
      (libsource (lib "CommonLib") (part "RES_SMD"))
    )
    (comp (ref "R57")
      (value "0.0")
      (footprint "R0402M")
      (description "RES SMD 0 OHM JUMPER 1/16W 0402")
      (fields (field (name "TOLERANCE") "1%"))
      (libsource (lib "CommonLib") (part "RES_SMD"))
    )
    (comp (ref "R58")
      (value "0.0")
      (footprint "R0402M")
      (description "RES SMD 0 OHM JUMPER 1/16W 0402")
      (fields (field (name "TOLERANCE") "1%"))
      (libsource (lib "CommonLib") (part "RES_SMD"))
    )
    (comp (ref "R59")
      (value "0.0")
      (footprint "R0402M")
      (description "RES SMD 0 OHM JUMPER 1/16W 0402")
      (fields (field (name "TOLERANCE") "1%"))
      (libsource (lib "CommonLib") (part "RES_SMD"))
    )
    (comp (ref "R60")
      (value "0.0")
      (footprint "R0402M")
      (description "RES SMD 0 OHM JUMPER 1/16W 0402")
      (fields (field (name "TOLERANCE") "1%"))
      (libsource (lib "CommonLib") (part "RES_SMD"))
    )
    (comp (ref "R61")
      (value "10k")
      (footprint "R0402M")
      (description "RES SMD 10K OHM 1% 1/16W 0402")
      (fields
        (field (name "MANUFACTURER") "Yageo")
        (field (name "MANUFACTURER PART NUMBER") "RC0402FR-0710KL")
        (field (name "CASE CODE (IMPERIAL)") "0402")
        (field (name "TOLERANCE") "1%")
      )
      (libsource (lib "CommonLib") (part "RES_SMD"))
    )
    (comp (ref "U1")
      (value "MIC2875-AYMT-T5")
      (footprint "SON50P200X60_HS-9N")
      (description "IC REG BOOST ADJ 3.8A 8TDFN")
      (libsource (lib "SmartToy") (part "MIC2875-AYMT-T5"))
    )
    (comp (ref "U2")
      (value "W25N01GVZEIG TR")
      (footprint "SON127P800X80_HS-9N")
      (description "IC FLASH 1G SPI 104MHZ 8WSON")
      (libsource (lib "SmartToy") (part "W25N01GVZEIG TR"))
    )
    (comp (ref "U3")
      (value "ESP32-S2")
      (footprint "QFN40P700X700X90_HS-57N")
      (description "RF System on a Chip - SoC SMD Wi-Fi IC, ESP32-S2, singal-core MCU, QFN 56-pin, 7*7 mm")
      (libsource (lib "SmartToy") (part "ESP32-S2"))
    )
    (comp (ref "U4")
      (value "AT42QT1110-MUR")
      (footprint "QFN50P500X500X100_HS-33N")
      (description "Capacitive Touch Screen 11 Key 32-Pin VQFN EP T/R")
      (libsource (lib "SmartToy") (part "AT42QT1110-MUR"))
    )
    (comp (ref "U5")
      (value "W25Q128JVSIM")
      (footprint "SOIC127P790X216-8N")
      (description "IC FLASH 128MBIT SPI/QUAD 8SOIC")
      (libsource (lib "SmartToy") (part "W25N01GVZEIG TR"))
    )
    (comp (ref "U6")
      (value "1909763-1")
      (footprint "IPEX_ANT")
      (description "CONN UMCC JACK STR 50OHM SMD")
      (fields (field (name "MANUFACTURER") "TE Connectivity AMP"))
      (libsource (lib "CommonLib") (part "AntenaIPX"))
    )
    (comp (ref "X1")
      (value "40MHz")
      (footprint "FA-128")
      (description "CRYSTAL 40.0000MHZ 8PF SMD")
      (libsource (lib "Vband") (part "FA-128 32.0000MF10Z-AJ3"))
    )
  )
  (nets
    (net (code "1") (name "+3.3V") (class "Default")
      (node (ref "C13") (pin "1") (pinfunction "1_1") (pintype "passive"))
      (node (ref "C14") (pin "1") (pinfunction "1_1") (pintype "passive"))
      (node (ref "C15") (pin "1") (pinfunction "1_1") (pintype "passive"))
      (node (ref "C23") (pin "1") (pinfunction "1_1") (pintype "passive"))
      (node (ref "C24") (pin "2") (pinfunction "2_2") (pintype "passive"))
      (node (ref "C29") (pin "2") (pinfunction "2_2") (pintype "passive"))
      (node (ref "C3") (pin "2") (pinfunction "2_2") (pintype "passive"))
      (node (ref "C30") (pin "2") (pinfunction "2_2") (pintype "passive"))
      (node (ref "C31") (pin "2") (pinfunction "2_2") (pintype "passive"))
      (node (ref "C32") (pin "2") (pinfunction "2_2") (pintype "passive"))
      (node (ref "C33") (pin "2") (pinfunction "2_2") (pintype "passive"))
      (node (ref "C34") (pin "2") (pinfunction "2_2") (pintype "passive"))
      (node (ref "C35") (pin "2") (pinfunction "2_2") (pintype "passive"))
      (node (ref "C36") (pin "2") (pinfunction "2_2") (pintype "passive"))
      (node (ref "C37") (pin "2") (pinfunction "2_2") (pintype "passive"))
      (node (ref "C4") (pin "2") (pinfunction "2_2") (pintype "passive"))
      (node (ref "C5") (pin "2") (pinfunction "2_2") (pintype "passive"))
      (node (ref "C6") (pin "2") (pinfunction "2_2") (pintype "passive"))
      (node (ref "C8") (pin "2") (pinfunction "2_2") (pintype "passive"))
      (node (ref "FB2") (pin "1") (pinfunction "1_1") (pintype "passive"))
      (node (ref "L3") (pin "1") (pinfunction "1_1") (pintype "passive"))
      (node (ref "P4") (pin "11") (pinfunction "11_11") (pintype "passive"))
      (node (ref "P6") (pin "3") (pinfunction "3_3") (pintype "passive"))
      (node (ref "R1") (pin "2") (pinfunction "2_2") (pintype "passive"))
      (node (ref "R20") (pin "2") (pinfunction "2_2") (pintype "passive"))
      (node (ref "R21") (pin "2") (pinfunction "2_2") (pintype "passive"))
      (node (ref "R22") (pin "2") (pinfunction "2_2") (pintype "passive"))
      (node (ref "R25") (pin "2") (pinfunction "2_2") (pintype "passive"))
      (node (ref "R26") (pin "2") (pinfunction "2_2") (pintype "passive"))
      (node (ref "R3") (pin "2") (pinfunction "2_2") (pintype "passive"))
      (node (ref "R37") (pin "2") (pinfunction "2_2") (pintype "passive"))
      (node (ref "R38") (pin "2") (pinfunction "2_2") (pintype "passive"))
      (node (ref "R39") (pin "2") (pinfunction "2_2") (pintype "passive"))
      (node (ref "R4") (pin "2") (pinfunction "2_2") (pintype "passive"))
      (node (ref "R40") (pin "2") (pinfunction "2_2") (pintype "passive"))
      (node (ref "R41") (pin "2") (pinfunction "2_2") (pintype "passive"))
      (node (ref "R42") (pin "2") (pinfunction "2_2") (pintype "passive"))
      (node (ref "R43") (pin "2") (pinfunction "2_2") (pintype "passive"))
      (node (ref "R44") (pin "2") (pinfunction "2_2") (pintype "passive"))
      (node (ref "R45") (pin "2") (pinfunction "2_2") (pintype "passive"))
      (node (ref "R54") (pin "2") (pinfunction "2_2") (pintype "passive"))
      (node (ref "R6") (pin "1") (pinfunction "1_1") (pintype "passive"))
      (node (ref "R61") (pin "2") (pinfunction "2_2") (pintype "passive"))
      (node (ref "R7") (pin "1") (pinfunction "1_1") (pintype "passive"))
      (node (ref "U1") (pin "8") (pinfunction "OUT_8") (pintype "passive"))
      (node (ref "U2") (pin "8") (pinfunction "VCC_8") (pintype "passive"))
      (node (ref "U3") (pin "1") (pinfunction "VDDA_1") (pintype "passive"))
      (node (ref "U3") (pin "20") (pinfunction "VDD3P3_RTC_20") (pintype "passive"))
      (node (ref "U3") (pin "27") (pinfunction "VDD3P3_RTC_IO_27") (pintype "passive"))
      (node (ref "U3") (pin "30") (pinfunction "VDD_SPI_30") (pintype "passive"))
      (node (ref "U3") (pin "45") (pinfunction "VDD3P3_CPU_45") (pintype "passive"))
      (node (ref "U3") (pin "54") (pinfunction "VDDA_54") (pintype "passive"))
      (node (ref "U4") (pin "18") (pinfunction "VDD_18") (pintype "passive"))
      (node (ref "U4") (pin "4") (pinfunction "VDD_4") (pintype "passive"))
      (node (ref "U5") (pin "8") (pinfunction "VCC_8") (pintype "passive"))
    )
    (net (code "2") (name "/BAT_IN") (class "Default")
      (node (ref "F1") (pin "1") (pinfunction "1_1") (pintype "passive"))
      (node (ref "P1") (pin "1") (pinfunction "1_1") (pintype "passive"))
    )
    (net (code "3") (name "/BOOK_MODE") (class "Default")
      (node (ref "R22") (pin "1") (pinfunction "1_1") (pintype "passive"))
      (node (ref "R27") (pin "1") (pinfunction "1_1") (pintype "passive"))
      (node (ref "U3") (pin "38") (pinfunction "GPIO34_38") (pintype "passive"))
    )
    (net (code "4") (name "/BUTTON") (class "Default")
      (node (ref "R36") (pin "1") (pinfunction "1_1") (pintype "passive"))
      (node (ref "R44") (pin "1") (pinfunction "1_1") (pintype "passive"))
      (node (ref "U3") (pin "28") (pinfunction "GPIO21_28") (pintype "passive"))
    )
    (net (code "5") (name "/D_N") (class "Default")
      (node (ref "R16") (pin "1") (pinfunction "1_1") (pintype "passive"))
      (node (ref "U3") (pin "25") (pinfunction "GPIO19_25") (pintype "passive"))
    )
    (net (code "6") (name "/D_P") (class "Default")
      (node (ref "R17") (pin "1") (pinfunction "1_1") (pintype "passive"))
      (node (ref "U3") (pin "26") (pinfunction "GPIO20_26") (pintype "passive"))
    )
    (net (code "7") (name "/ESP_EN") (class "Default")
      (node (ref "C21") (pin "2") (pinfunction "2_2") (pintype "passive"))
      (node (ref "P6") (pin "4") (pinfunction "4_4") (pintype "passive"))
      (node (ref "R25") (pin "1") (pinfunction "1_1") (pintype "passive"))
      (node (ref "U3") (pin "56") (pinfunction "CHIP_PU_56") (pintype "passive"))
    )
    (net (code "8") (name "/ESP_IO0") (class "Default")
      (node (ref "R26") (pin "1") (pinfunction "1_1") (pintype "passive"))
      (node (ref "R30") (pin "1") (pinfunction "1_1") (pintype "passive"))
      (node (ref "U3") (pin "5") (pinfunction "GPIO0_5") (pintype "passive"))
    )
    (net (code "9") (name "/ESP_IO0_FL") (class "Default")
      (node (ref "C22") (pin "2") (pinfunction "2_2") (pintype "passive"))
      (node (ref "P6") (pin "6") (pinfunction "6_6") (pintype "passive"))
      (node (ref "R30") (pin "2") (pinfunction "2_2") (pintype "passive"))
    )
    (net (code "10") (name "/ESP_RXD0") (class "Default")
      (node (ref "P6") (pin "2") (pinfunction "2_2") (pintype "passive"))
      (node (ref "U3") (pin "49") (pinfunction "U0RXD_49") (pintype "passive"))
    )
    (net (code "11") (name "/ESP_TXD0") (class "Default")
      (node (ref "P6") (pin "1") (pinfunction "1_1") (pintype "passive"))
      (node (ref "R55") (pin "2") (pinfunction "2_2") (pintype "passive"))
    )
    (net (code "12") (name "/FL_HOLD") (class "Default")
      (node (ref "R4") (pin "1") (pinfunction "1_1") (pintype "passive"))
      (node (ref "U2") (pin "7") (pinfunction "~{HOLD}(IO3)_7") (pintype "passive"))
      (node (ref "U3") (pin "40") (pinfunction "GPIO36_40") (pintype "passive"))
    )
    (net (code "13") (name "/FL_WP") (class "Default")
      (node (ref "U2") (pin "3") (pinfunction "~{WP}(IO2)_3") (pintype "passive"))
      (node (ref "U3") (pin "39") (pinfunction "GPIO35_39") (pintype "passive"))
    )
    (net (code "14") (name "/FUSE_OUT") (class "Default")
      (node (ref "F1") (pin "2") (pinfunction "2_2") (pintype "passive"))
      (node (ref "P4") (pin "4") (pinfunction "4_4") (pintype "passive"))
    )
    (net (code "15") (name "/LANGUE_SEL") (class "Default")
      (node (ref "R35") (pin "1") (pinfunction "1_1") (pintype "passive"))
      (node (ref "R45") (pin "1") (pinfunction "1_1") (pintype "passive"))
      (node (ref "U3") (pin "29") (pinfunction "SPICS1_29") (pintype "passive"))
    )
    (net (code "16") (name "/LED_K") (class "Default")
      (node (ref "R46") (pin "1") (pinfunction "1_1") (pintype "passive"))
      (node (ref "U3") (pin "18") (pinfunction "GPIO13_18") (pintype "passive"))
    )
    (net (code "17") (name "/LNA_IN") (class "Default")
      (node (ref "C26") (pin "2") (pinfunction "2_2") (pintype "passive"))
      (node (ref "L2") (pin "2") (pinfunction "2_2") (pintype "passive"))
      (node (ref "U3") (pin "2") (pinfunction "LNA_IN_2") (pintype "passive"))
    )
    (net (code "18") (name "/MCU_DAC1") (class "Default")
      (node (ref "P4") (pin "7") (pinfunction "7_7") (pintype "passive"))
      (node (ref "R29") (pin "2") (pinfunction "2_2") (pintype "passive"))
      (node (ref "U3") (pin "23") (pinfunction "DAC_1_23") (pintype "passive"))
    )
    (net (code "19") (name "/MCU_DAC2") (class "Default")
      (node (ref "R33") (pin "2") (pinfunction "2_2") (pintype "passive"))
      (node (ref "R61") (pin "1") (pinfunction "1_1") (pintype "passive"))
      (node (ref "U3") (pin "24") (pinfunction "DAC_2_24") (pintype "passive"))
    )
    (net (code "20") (name "/MCU_SL_PAGE2") (class "Default")
      (node (ref "R37") (pin "1") (pinfunction "1_1") (pintype "passive"))
      (node (ref "R47") (pin "1") (pinfunction "1_1") (pintype "passive"))
      (node (ref "U3") (pin "17") (pinfunction "GPIO12_17") (pintype "passive"))
    )
    (net (code "21") (name "/MCU_SL_PAGE3") (class "Default")
      (node (ref "R38") (pin "1") (pinfunction "1_1") (pintype "passive"))
      (node (ref "R48") (pin "1") (pinfunction "1_1") (pintype "passive"))
      (node (ref "U3") (pin "16") (pinfunction "GPIO11_16") (pintype "passive"))
    )
    (net (code "22") (name "/MCU_SL_PAGE4") (class "Default")
      (node (ref "R39") (pin "1") (pinfunction "1_1") (pintype "passive"))
      (node (ref "R49") (pin "1") (pinfunction "1_1") (pintype "passive"))
      (node (ref "U3") (pin "15") (pinfunction "GPIO10_15") (pintype "passive"))
    )
    (net (code "23") (name "/MCU_SL_PAGE5") (class "Default")
      (node (ref "R40") (pin "1") (pinfunction "1_1") (pintype "passive"))
      (node (ref "R50") (pin "1") (pinfunction "1_1") (pintype "passive"))
      (node (ref "U3") (pin "14") (pinfunction "GPIO9_14") (pintype "passive"))
    )
    (net (code "24") (name "/MCU_SL_PAGE6") (class "Default")
      (node (ref "R41") (pin "1") (pinfunction "1_1") (pintype "passive"))
      (node (ref "R51") (pin "1") (pinfunction "1_1") (pintype "passive"))
      (node (ref "U3") (pin "13") (pinfunction "GPIO8_13") (pintype "passive"))
    )
    (net (code "25") (name "/MCU_SL_PAGE7") (class "Default")
      (node (ref "R42") (pin "1") (pinfunction "1_1") (pintype "passive"))
      (node (ref "R52") (pin "1") (pinfunction "1_1") (pintype "passive"))
      (node (ref "U3") (pin "12") (pinfunction "GPIO7_12") (pintype "passive"))
    )
    (net (code "26") (name "/MCU_SL_PAGE8") (class "Default")
      (node (ref "R43") (pin "1") (pinfunction "1_1") (pintype "passive"))
      (node (ref "R53") (pin "1") (pinfunction "1_1") (pintype "passive"))
      (node (ref "U3") (pin "11") (pinfunction "GPIO6_11") (pintype "passive"))
    )
    (net (code "27") (name "/MUSIC_MODE") (class "Default")
      (node (ref "R21") (pin "1") (pinfunction "1_1") (pintype "passive"))
      (node (ref "R24") (pin "1") (pinfunction "1_1") (pintype "passive"))
      (node (ref "U3") (pin "37") (pinfunction "GPIO33_37") (pintype "passive"))
    )
    (net (code "28") (name "/SELECT_PAGE2") (class "Default")
      (node (ref "P8") (pin "1") (pinfunction "1_1") (pintype "passive"))
      (node (ref "R47") (pin "2") (pinfunction "2_2") (pintype "passive"))
    )
    (net (code "29") (name "/SELECT_PAGE3") (class "Default")
      (node (ref "P8") (pin "2") (pinfunction "2_2") (pintype "passive"))
      (node (ref "R48") (pin "2") (pinfunction "2_2") (pintype "passive"))
    )
    (net (code "30") (name "/SELECT_PAGE4") (class "Default")
      (node (ref "P8") (pin "3") (pinfunction "3_3") (pintype "passive"))
      (node (ref "R49") (pin "2") (pinfunction "2_2") (pintype "passive"))
    )
    (net (code "31") (name "/SELECT_PAGE5") (class "Default")
      (node (ref "P8") (pin "4") (pinfunction "4_4") (pintype "passive"))
      (node (ref "R50") (pin "2") (pinfunction "2_2") (pintype "passive"))
    )
    (net (code "32") (name "/SELECT_PAGE6") (class "Default")
      (node (ref "P8") (pin "5") (pinfunction "5_5") (pintype "passive"))
      (node (ref "R51") (pin "2") (pinfunction "2_2") (pintype "passive"))
    )
    (net (code "33") (name "/SELECT_PAGE7") (class "Default")
      (node (ref "P8") (pin "6") (pinfunction "6_6") (pintype "passive"))
      (node (ref "R52") (pin "2") (pinfunction "2_2") (pintype "passive"))
    )
    (net (code "34") (name "/SELECT_PAGE8") (class "Default")
      (node (ref "P8") (pin "7") (pinfunction "7_7") (pintype "passive"))
      (node (ref "R53") (pin "2") (pinfunction "2_2") (pintype "passive"))
    )
    (net (code "35") (name "/SPI2_CLK") (class "Default")
      (node (ref "U2") (pin "6") (pinfunction "CLK_6") (pintype "passive"))
      (node (ref "U3") (pin "41") (pinfunction "GPIO37_41") (pintype "passive"))
    )
    (net (code "36") (name "/SPI2_CS") (class "Default")
      (node (ref "R1") (pin "1") (pinfunction "1_1") (pintype "passive"))
      (node (ref "U2") (pin "1") (pinfunction "~{CS}_1") (pintype "passive"))
      (node (ref "U3") (pin "44") (pinfunction "MTD0_44") (pintype "passive"))
    )
    (net (code "37") (name "/SPI2_MISO") (class "Default")
      (node (ref "U2") (pin "2") (pinfunction "DO(IO1)_2") (pintype "passive"))
      (node (ref "U3") (pin "42") (pinfunction "GPIO38_42") (pintype "passive"))
    )
    (net (code "38") (name "/SPI2_MOSI") (class "Default")
      (node (ref "U2") (pin "5") (pinfunction "DI(IO0)_5") (pintype "passive"))
      (node (ref "U3") (pin "43") (pinfunction "MTCK_43") (pintype "passive"))
    )
    (net (code "39") (name "/SPI3_MISO") (class "Default")
      (node (ref "R28") (pin "1") (pinfunction "1_1") (pintype "passive"))
      (node (ref "U3") (pin "6") (pinfunction "GPIO1_6") (pintype "passive"))
      (node (ref "U4") (pin "15") (pinfunction "MISO_15") (pintype "passive"))
    )
    (net (code "40") (name "/SPI3_MOSI") (class "Default")
      (node (ref "R32") (pin "1") (pinfunction "1_1") (pintype "passive"))
      (node (ref "U3") (pin "7") (pinfunction "GPIO2_7") (pintype "passive"))
      (node (ref "U4") (pin "16") (pinfunction "MOSI_16") (pintype "passive"))
    )
    (net (code "41") (name "/SPI3_SCK") (class "Default")
      (node (ref "R34") (pin "1") (pinfunction "1_1") (pintype "passive"))
      (node (ref "U3") (pin "8") (pinfunction "GPIO3_8") (pintype "passive"))
      (node (ref "U4") (pin "17") (pinfunction "SCK_17") (pintype "passive"))
    )
    (net (code "42") (name "/SPICLK") (class "Default")
      (node (ref "R58") (pin "2") (pinfunction "2_2") (pintype "passive"))
      (node (ref "U5") (pin "6") (pinfunction "CLK_6") (pintype "passive"))
    )
    (net (code "43") (name "/SPICS0") (class "Default")
      (node (ref "R54") (pin "1") (pinfunction "1_1") (pintype "passive"))
      (node (ref "U3") (pin "33") (pinfunction "SPICS0_33") (pintype "passive"))
      (node (ref "U5") (pin "1") (pinfunction "~{CS}_1") (pintype "passive"))
    )
    (net (code "44") (name "/SPID") (class "Default")
      (node (ref "R56") (pin "2") (pinfunction "2_2") (pintype "passive"))
      (node (ref "U5") (pin "5") (pinfunction "DI(IO0)_5") (pintype "passive"))
    )
    (net (code "45") (name "/SPIHD") (class "Default")
      (node (ref "R60") (pin "2") (pinfunction "2_2") (pintype "passive"))
      (node (ref "U5") (pin "7") (pinfunction "~{HOLD}(IO3)_7") (pintype "passive"))
    )
    (net (code "46") (name "/SPIQ") (class "Default")
      (node (ref "R57") (pin "2") (pinfunction "2_2") (pintype "passive"))
      (node (ref "U5") (pin "2") (pinfunction "DO(IO1)_2") (pintype "passive"))
    )
    (net (code "47") (name "/SPIWP") (class "Default")
      (node (ref "R59") (pin "2") (pinfunction "2_2") (pintype "passive"))
      (node (ref "U5") (pin "3") (pinfunction "~{WP}(IO2)_3") (pintype "passive"))
    )
    (net (code "48") (name "/SPK1") (class "Default")
      (node (ref "P4") (pin "8") (pinfunction "8_8") (pintype "passive"))
      (node (ref "P7") (pin "1") (pinfunction "1_1") (pintype "passive"))
      (node (ref "R29") (pin "1") (pinfunction "1_1") (pintype "passive"))
    )
    (net (code "49") (name "/SPK2") (class "Default")
      (node (ref "P7") (pin "2") (pinfunction "2_2") (pintype "passive"))
      (node (ref "R33") (pin "1") (pinfunction "1_1") (pintype "passive"))
    )
    (net (code "50") (name "/TOUCH_CH0") (class "Default")
      (node (ref "P2") (pin "7") (pinfunction "7_7") (pintype "passive"))
      (node (ref "R8") (pin "1") (pinfunction "1_1") (pintype "passive"))
    )
    (net (code "51") (name "/TOUCH_CH1") (class "Default")
      (node (ref "P2") (pin "6") (pinfunction "6_6") (pintype "passive"))
      (node (ref "R9") (pin "1") (pinfunction "1_1") (pintype "passive"))
    )
    (net (code "52") (name "/TOUCH_CH2") (class "Default")
      (node (ref "P2") (pin "5") (pinfunction "5_5") (pintype "passive"))
      (node (ref "R10") (pin "1") (pinfunction "1_1") (pintype "passive"))
    )
    (net (code "53") (name "/TOUCH_CH3") (class "Default")
      (node (ref "P2") (pin "4") (pinfunction "4_4") (pintype "passive"))
      (node (ref "R11") (pin "1") (pinfunction "1_1") (pintype "passive"))
    )
    (net (code "54") (name "/TOUCH_CH4") (class "Default")
      (node (ref "P2") (pin "3") (pinfunction "3_3") (pintype "passive"))
      (node (ref "R12") (pin "1") (pinfunction "1_1") (pintype "passive"))
    )
    (net (code "55") (name "/TOUCH_CH5") (class "Default")
      (node (ref "P2") (pin "2") (pinfunction "2_2") (pintype "passive"))
      (node (ref "R13") (pin "1") (pinfunction "1_1") (pintype "passive"))
    )
    (net (code "56") (name "/TOUCH_CH6") (class "Default")
      (node (ref "P2") (pin "11") (pinfunction "11_11") (pintype "passive"))
      (node (ref "R14") (pin "1") (pinfunction "1_1") (pintype "passive"))
    )
    (net (code "57") (name "/TOUCH_CH7") (class "Default")
      (node (ref "P2") (pin "10") (pinfunction "10_10") (pintype "passive"))
      (node (ref "R15") (pin "1") (pinfunction "1_1") (pintype "passive"))
    )
    (net (code "58") (name "/TOUCH_CH8") (class "Default")
      (node (ref "P2") (pin "9") (pinfunction "9_9") (pintype "passive"))
      (node (ref "R18") (pin "1") (pinfunction "1_1") (pintype "passive"))
    )
    (net (code "59") (name "/TOUCH_CH9") (class "Default")
      (node (ref "P2") (pin "8") (pinfunction "8_8") (pintype "passive"))
      (node (ref "R19") (pin "1") (pinfunction "1_1") (pintype "passive"))
    )
    (net (code "60") (name "/TOUCH_SS1") (class "Default")
      (node (ref "U3") (pin "9") (pinfunction "GPIO4_9") (pintype "passive"))
      (node (ref "U4") (pin "14") (pinfunction "~{SS}_14") (pintype "passive"))
    )
    (net (code "61") (name "/TOUCH_SS2") (class "Default")
      (node (ref "R23") (pin "1") (pinfunction "1_1") (pintype "passive"))
      (node (ref "U3") (pin "10") (pinfunction "GPIO5_10") (pintype "passive"))
    )
    (net (code "62") (name "/USB_D_N") (class "Default")
      (node (ref "P3") (pin "1") (pinfunction "1_1") (pintype "passive"))
      (node (ref "R16") (pin "2") (pinfunction "2_2") (pintype "passive"))
    )
    (net (code "63") (name "/USB_D_P") (class "Default")
      (node (ref "P3") (pin "2") (pinfunction "2_2") (pintype "passive"))
      (node (ref "R17") (pin "2") (pinfunction "2_2") (pintype "passive"))
    )
    (net (code "64") (name "/XTAL_N") (class "Default")
      (node (ref "C28") (pin "2") (pinfunction "2_2") (pintype "passive"))
      (node (ref "U3") (pin "52") (pinfunction "XTAL_N_52") (pintype "passive"))
      (node (ref "X1") (pin "1") (pinfunction "1_1") (pintype "passive"))
    )
    (net (code "65") (name "/XTAL_P") (class "Default")
      (node (ref "C27") (pin "2") (pinfunction "2_2") (pintype "passive"))
      (node (ref "U3") (pin "53") (pinfunction "XTAL_P_53") (pintype "passive"))
      (node (ref "X1") (pin "3") (pinfunction "3_3") (pintype "passive"))
    )
    (net (code "66") (name "GND") (class "Default")
      (node (ref "C1") (pin "2") (pinfunction "2_2") (pintype "passive"))
      (node (ref "C13") (pin "2") (pinfunction "2_2") (pintype "passive"))
      (node (ref "C14") (pin "2") (pinfunction "2_2") (pintype "passive"))
      (node (ref "C15") (pin "2") (pinfunction "2_2") (pintype "passive"))
      (node (ref "C2") (pin "2") (pinfunction "2_2") (pintype "passive"))
      (node (ref "C21") (pin "1") (pinfunction "1_1") (pintype "passive"))
      (node (ref "C22") (pin "1") (pinfunction "1_1") (pintype "passive"))
      (node (ref "C23") (pin "2") (pinfunction "2_2") (pintype "passive"))
      (node (ref "C24") (pin "1") (pinfunction "1_1") (pintype "passive"))
      (node (ref "C25") (pin "1") (pinfunction "1_1") (pintype "passive"))
      (node (ref "C26") (pin "1") (pinfunction "1_1") (pintype "passive"))
      (node (ref "C27") (pin "1") (pinfunction "1_1") (pintype "passive"))
      (node (ref "C28") (pin "1") (pinfunction "1_1") (pintype "passive"))
      (node (ref "C29") (pin "1") (pinfunction "1_1") (pintype "passive"))
      (node (ref "C3") (pin "1") (pinfunction "1_1") (pintype "passive"))
      (node (ref "C30") (pin "1") (pinfunction "1_1") (pintype "passive"))
      (node (ref "C31") (pin "1") (pinfunction "1_1") (pintype "passive"))
      (node (ref "C32") (pin "1") (pinfunction "1_1") (pintype "passive"))
      (node (ref "C33") (pin "1") (pinfunction "1_1") (pintype "passive"))
      (node (ref "C34") (pin "1") (pinfunction "1_1") (pintype "passive"))
      (node (ref "C35") (pin "1") (pinfunction "1_1") (pintype "passive"))
      (node (ref "C36") (pin "1") (pinfunction "1_1") (pintype "passive"))
      (node (ref "C37") (pin "1") (pinfunction "1_1") (pintype "passive"))
      (node (ref "C38") (pin "1") (pinfunction "1_1") (pintype "passive"))
      (node (ref "C4") (pin "1") (pinfunction "1_1") (pintype "passive"))
      (node (ref "C5") (pin "1") (pinfunction "1_1") (pintype "passive"))
      (node (ref "C6") (pin "1") (pinfunction "1_1") (pintype "passive"))
      (node (ref "C8") (pin "1") (pinfunction "1_1") (pintype "passive"))
      (node (ref "FB1") (pin "1") (pinfunction "1_1") (pintype "passive"))
      (node (ref "P1") (pin "2") (pinfunction "2_2") (pintype "passive"))
      (node (ref "P2") (pin "1") (pinfunction "1_1") (pintype "passive"))
      (node (ref "P3") (pin "3") (pinfunction "3_3") (pintype "passive"))
      (node (ref "P4") (pin "1") (pinfunction "1_1") (pintype "passive"))
      (node (ref "P6") (pin "5") (pinfunction "5_5") (pintype "passive"))
      (node (ref "P8") (pin "8") (pinfunction "8_8") (pintype "passive"))
      (node (ref "R31") (pin "1") (pinfunction "1_1") (pintype "passive"))
      (node (ref "R5") (pin "1") (pinfunction "1_1") (pintype "passive"))
      (node (ref "U1") (pin "2") (pinfunction "PGND_2") (pintype "passive"))
      (node (ref "U1") (pin "4") (pinfunction "AGND_4") (pintype "passive"))
      (node (ref "U1") (pin "9") (pinfunction "PAD_9") (pintype "passive"))
      (node (ref "U2") (pin "4") (pinfunction "GND_4") (pintype "passive"))
      (node (ref "U3") (pin "57") (pinfunction "PAD_57") (pintype "passive"))
      (node (ref "U4") (pin "21") (pinfunction "VSS_21") (pintype "passive"))
      (node (ref "U4") (pin "33") (pinfunction "PAD_33") (pintype "passive"))
      (node (ref "U4") (pin "5") (pinfunction "VSS_5") (pintype "passive"))
      (node (ref "U5") (pin "4") (pinfunction "GND_4") (pintype "passive"))
      (node (ref "U6") (pin "2") (pinfunction "GND_2") (pintype "passive"))
      (node (ref "X1") (pin "2") (pinfunction "2_2") (pintype "passive"))
      (node (ref "X1") (pin "4") (pinfunction "4_4") (pintype "passive"))
    )
    (net (code "67") (name "Net-(FB1-Pad2)") (class "Default")
      (node (ref "FB1") (pin "2") (pinfunction "2_2") (pintype "passive"))
      (node (ref "P5") (pin "2") (pinfunction "2_2") (pintype "passive"))
    )
    (net (code "68") (name "Net-(FB2-Pad2)") (class "Default")
      (node (ref "FB2") (pin "2") (pinfunction "2_2") (pintype "passive"))
      (node (ref "P5") (pin "3") (pinfunction "3_3") (pintype "passive"))
    )
    (net (code "69") (name "Net-(P4-Pad2)") (class "Default")
      (node (ref "P4") (pin "2") (pinfunction "2_2") (pintype "passive"))
      (node (ref "R24") (pin "2") (pinfunction "2_2") (pintype "passive"))
    )
    (net (code "70") (name "Net-(P4-Pad3)") (class "Default")
      (node (ref "P4") (pin "3") (pinfunction "3_3") (pintype "passive"))
      (node (ref "R27") (pin "2") (pinfunction "2_2") (pintype "passive"))
    )
    (net (code "71") (name "Net-(P4-Pad5)") (class "Default")
      (node (ref "P4") (pin "5") (pinfunction "5_5") (pintype "passive"))
      (node (ref "R31") (pin "2") (pinfunction "2_2") (pintype "passive"))
    )
    (net (code "72") (name "Net-(P4-Pad9)") (class "Default")
      (node (ref "P4") (pin "9") (pinfunction "9_9") (pintype "passive"))
      (node (ref "R35") (pin "2") (pinfunction "2_2") (pintype "passive"))
    )
    (net (code "73") (name "Net-(P4-Pad10)") (class "Default")
      (node (ref "P4") (pin "10") (pinfunction "10_10") (pintype "passive"))
      (node (ref "R36") (pin "2") (pinfunction "2_2") (pintype "passive"))
    )
    (net (code "74") (name "Net-(P4-Pad12)") (class "Default")
      (node (ref "P4") (pin "12") (pinfunction "12_12") (pintype "passive"))
      (node (ref "R46") (pin "2") (pinfunction "2_2") (pintype "passive"))
    )
    (net (code "75") (name "Net-(P5-Pad1)") (class "Default")
      (node (ref "P5") (pin "1") (pinfunction "1_1") (pintype "passive"))
      (node (ref "R23") (pin "2") (pinfunction "2_2") (pintype "passive"))
    )
    (net (code "76") (name "Net-(P5-Pad4)") (class "Default")
      (node (ref "P5") (pin "4") (pinfunction "4_4") (pintype "passive"))
      (node (ref "R28") (pin "2") (pinfunction "2_2") (pintype "passive"))
    )
    (net (code "77") (name "Net-(P5-Pad5)") (class "Default")
      (node (ref "P5") (pin "5") (pinfunction "5_5") (pintype "passive"))
      (node (ref "R32") (pin "2") (pinfunction "2_2") (pintype "passive"))
    )
    (net (code "78") (name "Net-(P5-Pad6)") (class "Default")
      (node (ref "P5") (pin "6") (pinfunction "6_6") (pintype "passive"))
      (node (ref "R34") (pin "2") (pinfunction "2_2") (pintype "passive"))
    )
    (net (code "79") (name "Net-(U1-FB)") (class "Default")
      (node (ref "R3") (pin "1") (pinfunction "1_1") (pintype "passive"))
      (node (ref "R5") (pin "2") (pinfunction "2_2") (pintype "passive"))
      (node (ref "U1") (pin "5") (pinfunction "FB_5") (pintype "passive"))
    )
    (net (code "80") (name "Net-(U1-SW)") (class "Default")
      (node (ref "L1") (pin "2") (pinfunction "2_2") (pintype "passive"))
      (node (ref "U1") (pin "1") (pinfunction "SW_1") (pintype "passive"))
    )
    (net (code "81") (name "Net-(U1-~{PG})") (class "Default")
      (node (ref "R2") (pin "2") (pinfunction "2_2") (pintype "passive"))
      (node (ref "U1") (pin "7") (pinfunction "~{PG}_7") (pintype "passive"))
    )
    (net (code "82") (name "Net-(U3-SPICLK)") (class "Default")
      (node (ref "R58") (pin "1") (pinfunction "1_1") (pintype "passive"))
      (node (ref "U3") (pin "34") (pinfunction "SPICLK_34") (pintype "passive"))
    )
    (net (code "83") (name "Net-(U3-SPID)") (class "Default")
      (node (ref "R56") (pin "1") (pinfunction "1_1") (pintype "passive"))
      (node (ref "U3") (pin "36") (pinfunction "SPID_36") (pintype "passive"))
    )
    (net (code "84") (name "Net-(U3-SPIHD)") (class "Default")
      (node (ref "R60") (pin "1") (pinfunction "1_1") (pintype "passive"))
      (node (ref "U3") (pin "31") (pinfunction "SPIHD_31") (pintype "passive"))
    )
    (net (code "85") (name "Net-(U3-SPIQ)") (class "Default")
      (node (ref "R57") (pin "1") (pinfunction "1_1") (pintype "passive"))
      (node (ref "U3") (pin "35") (pinfunction "SPIQ_35") (pintype "passive"))
    )
    (net (code "86") (name "Net-(U3-SPIWP)") (class "Default")
      (node (ref "R59") (pin "1") (pinfunction "1_1") (pintype "passive"))
      (node (ref "U3") (pin "32") (pinfunction "SPIWP_32") (pintype "passive"))
    )
    (net (code "87") (name "Net-(U3-U0TXD)") (class "Default")
      (node (ref "R55") (pin "1") (pinfunction "1_1") (pintype "passive"))
      (node (ref "U3") (pin "48") (pinfunction "U0TXD_48") (pintype "passive"))
    )
    (net (code "88") (name "Net-(U4-SNS0)") (class "Default")
      (node (ref "C7") (pin "2") (pinfunction "2_2") (pintype "passive"))
      (node (ref "U4") (pin "32") (pinfunction "SNS0_32") (pintype "passive"))
    )
    (net (code "89") (name "Net-(U4-SNS0K)") (class "Default")
      (node (ref "C7") (pin "1") (pinfunction "1_1") (pintype "passive"))
      (node (ref "R8") (pin "2") (pinfunction "2_2") (pintype "passive"))
      (node (ref "U4") (pin "1") (pinfunction "SNS0K_1") (pintype "passive"))
    )
    (net (code "90") (name "Net-(U4-SNS1)") (class "Default")
      (node (ref "C9") (pin "2") (pinfunction "2_2") (pintype "passive"))
      (node (ref "U4") (pin "2") (pinfunction "SNS1_2") (pintype "passive"))
    )
    (net (code "91") (name "Net-(U4-SNS1K)") (class "Default")
      (node (ref "C9") (pin "1") (pinfunction "1_1") (pintype "passive"))
      (node (ref "R9") (pin "2") (pinfunction "2_2") (pintype "passive"))
      (node (ref "U4") (pin "3") (pinfunction "SNS1K_3") (pintype "passive"))
    )
    (net (code "92") (name "Net-(U4-SNS2)") (class "Default")
      (node (ref "C10") (pin "2") (pinfunction "2_2") (pintype "passive"))
      (node (ref "U4") (pin "7") (pinfunction "SNS2_7") (pintype "passive"))
    )
    (net (code "93") (name "Net-(U4-SNS2K)") (class "Default")
      (node (ref "C10") (pin "1") (pinfunction "1_1") (pintype "passive"))
      (node (ref "R10") (pin "2") (pinfunction "2_2") (pintype "passive"))
      (node (ref "U4") (pin "6") (pinfunction "SNS2K_6") (pintype "passive"))
    )
    (net (code "94") (name "Net-(U4-SNS3)") (class "Default")
      (node (ref "C11") (pin "2") (pinfunction "2_2") (pintype "passive"))
      (node (ref "U4") (pin "8") (pinfunction "SNS3_8") (pintype "passive"))
    )
    (net (code "95") (name "Net-(U4-SNS3K)") (class "Default")
      (node (ref "C11") (pin "1") (pinfunction "1_1") (pintype "passive"))
      (node (ref "R11") (pin "2") (pinfunction "2_2") (pintype "passive"))
      (node (ref "U4") (pin "9") (pinfunction "SNS3K_9") (pintype "passive"))
    )
    (net (code "96") (name "Net-(U4-SNS4)") (class "Default")
      (node (ref "C12") (pin "2") (pinfunction "2_2") (pintype "passive"))
      (node (ref "U4") (pin "10") (pinfunction "SNS4_10") (pintype "passive"))
    )
    (net (code "97") (name "Net-(U4-SNS4K)") (class "Default")
      (node (ref "C12") (pin "1") (pinfunction "1_1") (pintype "passive"))
      (node (ref "R12") (pin "2") (pinfunction "2_2") (pintype "passive"))
      (node (ref "U4") (pin "11") (pinfunction "SNS4K_11") (pintype "passive"))
    )
    (net (code "98") (name "Net-(U4-SNS5)") (class "Default")
      (node (ref "C16") (pin "2") (pinfunction "2_2") (pintype "passive"))
      (node (ref "U4") (pin "12") (pinfunction "SNS5_12") (pintype "passive"))
    )
    (net (code "99") (name "Net-(U4-SNS5K)") (class "Default")
      (node (ref "C16") (pin "1") (pinfunction "1_1") (pintype "passive"))
      (node (ref "R13") (pin "2") (pinfunction "2_2") (pintype "passive"))
      (node (ref "U4") (pin "13") (pinfunction "SNS5K_13") (pintype "passive"))
    )
    (net (code "100") (name "Net-(U4-SNS6)") (class "Default")
      (node (ref "C17") (pin "2") (pinfunction "2_2") (pintype "passive"))
      (node (ref "U4") (pin "20") (pinfunction "SNS6_20") (pintype "passive"))
    )
    (net (code "101") (name "Net-(U4-SNS6K)") (class "Default")
      (node (ref "C17") (pin "1") (pinfunction "1_1") (pintype "passive"))
      (node (ref "R14") (pin "2") (pinfunction "2_2") (pintype "passive"))
      (node (ref "U4") (pin "19") (pinfunction "SNS6K_19") (pintype "passive"))
    )
    (net (code "102") (name "Net-(U4-SNS7K{slash}DETECT0)") (class "Default")
      (node (ref "C18") (pin "1") (pinfunction "1_1") (pintype "passive"))
      (node (ref "R15") (pin "2") (pinfunction "2_2") (pintype "passive"))
      (node (ref "U4") (pin "22") (pinfunction "SNS7K/DETECT0_22") (pintype "passive"))
    )
    (net (code "103") (name "Net-(U4-SNS7{slash}DETECT1)") (class "Default")
      (node (ref "C18") (pin "2") (pinfunction "2_2") (pintype "passive"))
      (node (ref "U4") (pin "23") (pinfunction "SNS7/DETECT1_23") (pintype "passive"))
    )
    (net (code "104") (name "Net-(U4-SNS8K{slash}DETECT3)") (class "Default")
      (node (ref "C19") (pin "1") (pinfunction "1_1") (pintype "passive"))
      (node (ref "R18") (pin "2") (pinfunction "2_2") (pintype "passive"))
      (node (ref "U4") (pin "25") (pinfunction "SNS8K/DETECT3_25") (pintype "passive"))
    )
    (net (code "105") (name "Net-(U4-SNS8{slash}DETECT2)") (class "Default")
      (node (ref "C19") (pin "2") (pinfunction "2_2") (pintype "passive"))
      (node (ref "U4") (pin "24") (pinfunction "SNS8/DETECT2_24") (pintype "passive"))
    )
    (net (code "106") (name "Net-(U4-SNS9K{slash}DETECT5)") (class "Default")
      (node (ref "C20") (pin "1") (pinfunction "1_1") (pintype "passive"))
      (node (ref "R19") (pin "2") (pinfunction "2_2") (pintype "passive"))
      (node (ref "U4") (pin "27") (pinfunction "SNS9K/DETECT5_27") (pintype "passive"))
    )
    (net (code "107") (name "Net-(U4-SNS9{slash}DETECT4)") (class "Default")
      (node (ref "C20") (pin "2") (pinfunction "2_2") (pintype "passive"))
      (node (ref "U4") (pin "26") (pinfunction "SNS9/DETECT4_26") (pintype "passive"))
    )
    (net (code "108") (name "Net-(U4-SNS10K{slash}SYNC)") (class "Default")
      (node (ref "R20") (pin "1") (pinfunction "1_1") (pintype "passive"))
      (node (ref "U4") (pin "31") (pinfunction "SNS10K/SYNC_31") (pintype "passive"))
    )
    (net (code "109") (name "Net-(U4-~{CHANGE})") (class "Default")
      (node (ref "R6") (pin "2") (pinfunction "2_2") (pintype "passive"))
      (node (ref "U4") (pin "28") (pinfunction "~{CHANGE}_28") (pintype "passive"))
    )
    (net (code "110") (name "Net-(U4-~{RESET})") (class "Default")
      (node (ref "R7") (pin "2") (pinfunction "2_2") (pintype "passive"))
      (node (ref "U4") (pin "29") (pinfunction "~{RESET}_29") (pintype "passive"))
    )
    (net (code "111") (name "Net-(U6-SIG)") (class "Default")
      (node (ref "C25") (pin "2") (pinfunction "2_2") (pintype "passive"))
      (node (ref "L2") (pin "1") (pinfunction "1_1") (pintype "passive"))
      (node (ref "U6") (pin "1") (pinfunction "SIG_1") (pintype "passive"))
    )
    (net (code "112") (name "PWR_IN") (class "Default")
      (node (ref "C1") (pin "1") (pinfunction "1_1") (pintype "passive"))
      (node (ref "C2") (pin "1") (pinfunction "1_1") (pintype "passive"))
      (node (ref "L1") (pin "1") (pinfunction "1_1") (pintype "passive"))
      (node (ref "P4") (pin "6") (pinfunction "6_6") (pintype "passive"))
      (node (ref "R2") (pin "1") (pinfunction "1_1") (pintype "passive"))
      (node (ref "U1") (pin "3") (pinfunction "IN_3") (pintype "passive"))
      (node (ref "U1") (pin "6") (pinfunction "EN_6") (pintype "passive"))
    )
    (net (code "113") (name "VDD3P3") (class "Default")
      (node (ref "C38") (pin "2") (pinfunction "2_2") (pintype "passive"))
      (node (ref "L3") (pin "2") (pinfunction "2_2") (pintype "passive"))
      (node (ref "U3") (pin "3") (pinfunction "VDD3P3_3") (pintype "passive"))
      (node (ref "U3") (pin "4") (pinfunction "VDD3P3_4") (pintype "passive"))
    )
    (net (code "114") (name "unconnected-(U3-GPIO14-Pad19)") (class "Default")
      (node (ref "U3") (pin "19") (pinfunction "GPIO14_19") (pintype "passive"))
    )
    (net (code "115") (name "unconnected-(U3-GPIO45-Pad50)") (class "Default")
      (node (ref "U3") (pin "50") (pinfunction "GPIO45_50") (pintype "passive"))
    )
    (net (code "116") (name "unconnected-(U3-GPIO46-Pad55)") (class "Default")
      (node (ref "U3") (pin "55") (pinfunction "GPIO46_55") (pintype "passive"))
    )
    (net (code "117") (name "unconnected-(U3-MTDI-Pad46)") (class "Default")
      (node (ref "U3") (pin "46") (pinfunction "MTDI_46") (pintype "passive"))
    )
    (net (code "118") (name "unconnected-(U3-MTMS-Pad47)") (class "Default")
      (node (ref "U3") (pin "47") (pinfunction "MTMS_47") (pintype "passive"))
    )
    (net (code "119") (name "unconnected-(U3-VDDA-Pad51)") (class "Default")
      (node (ref "U3") (pin "51") (pinfunction "VDDA_51") (pintype "passive"))
    )
    (net (code "120") (name "unconnected-(U3-XTAL_32K_N-Pad22)") (class "Default")
      (node (ref "U3") (pin "22") (pinfunction "XTAL_32K_N_22") (pintype "passive"))
    )
    (net (code "121") (name "unconnected-(U3-XTAL_32K_P-Pad21)") (class "Default")
      (node (ref "U3") (pin "21") (pinfunction "XTAL_32K_P_21") (pintype "passive"))
    )
    (net (code "122") (name "unconnected-(U4-SNS10{slash}DETECT6-Pad30)") (class "Default")
      (node (ref "U4") (pin "30") (pinfunction "SNS10/DETECT6_30") (pintype "passive+no_connect"))
    )
  )
)
